# PixelScreen_WS2812B.net
KiCad netlist of a schematic drawn in EasyEDA Pro
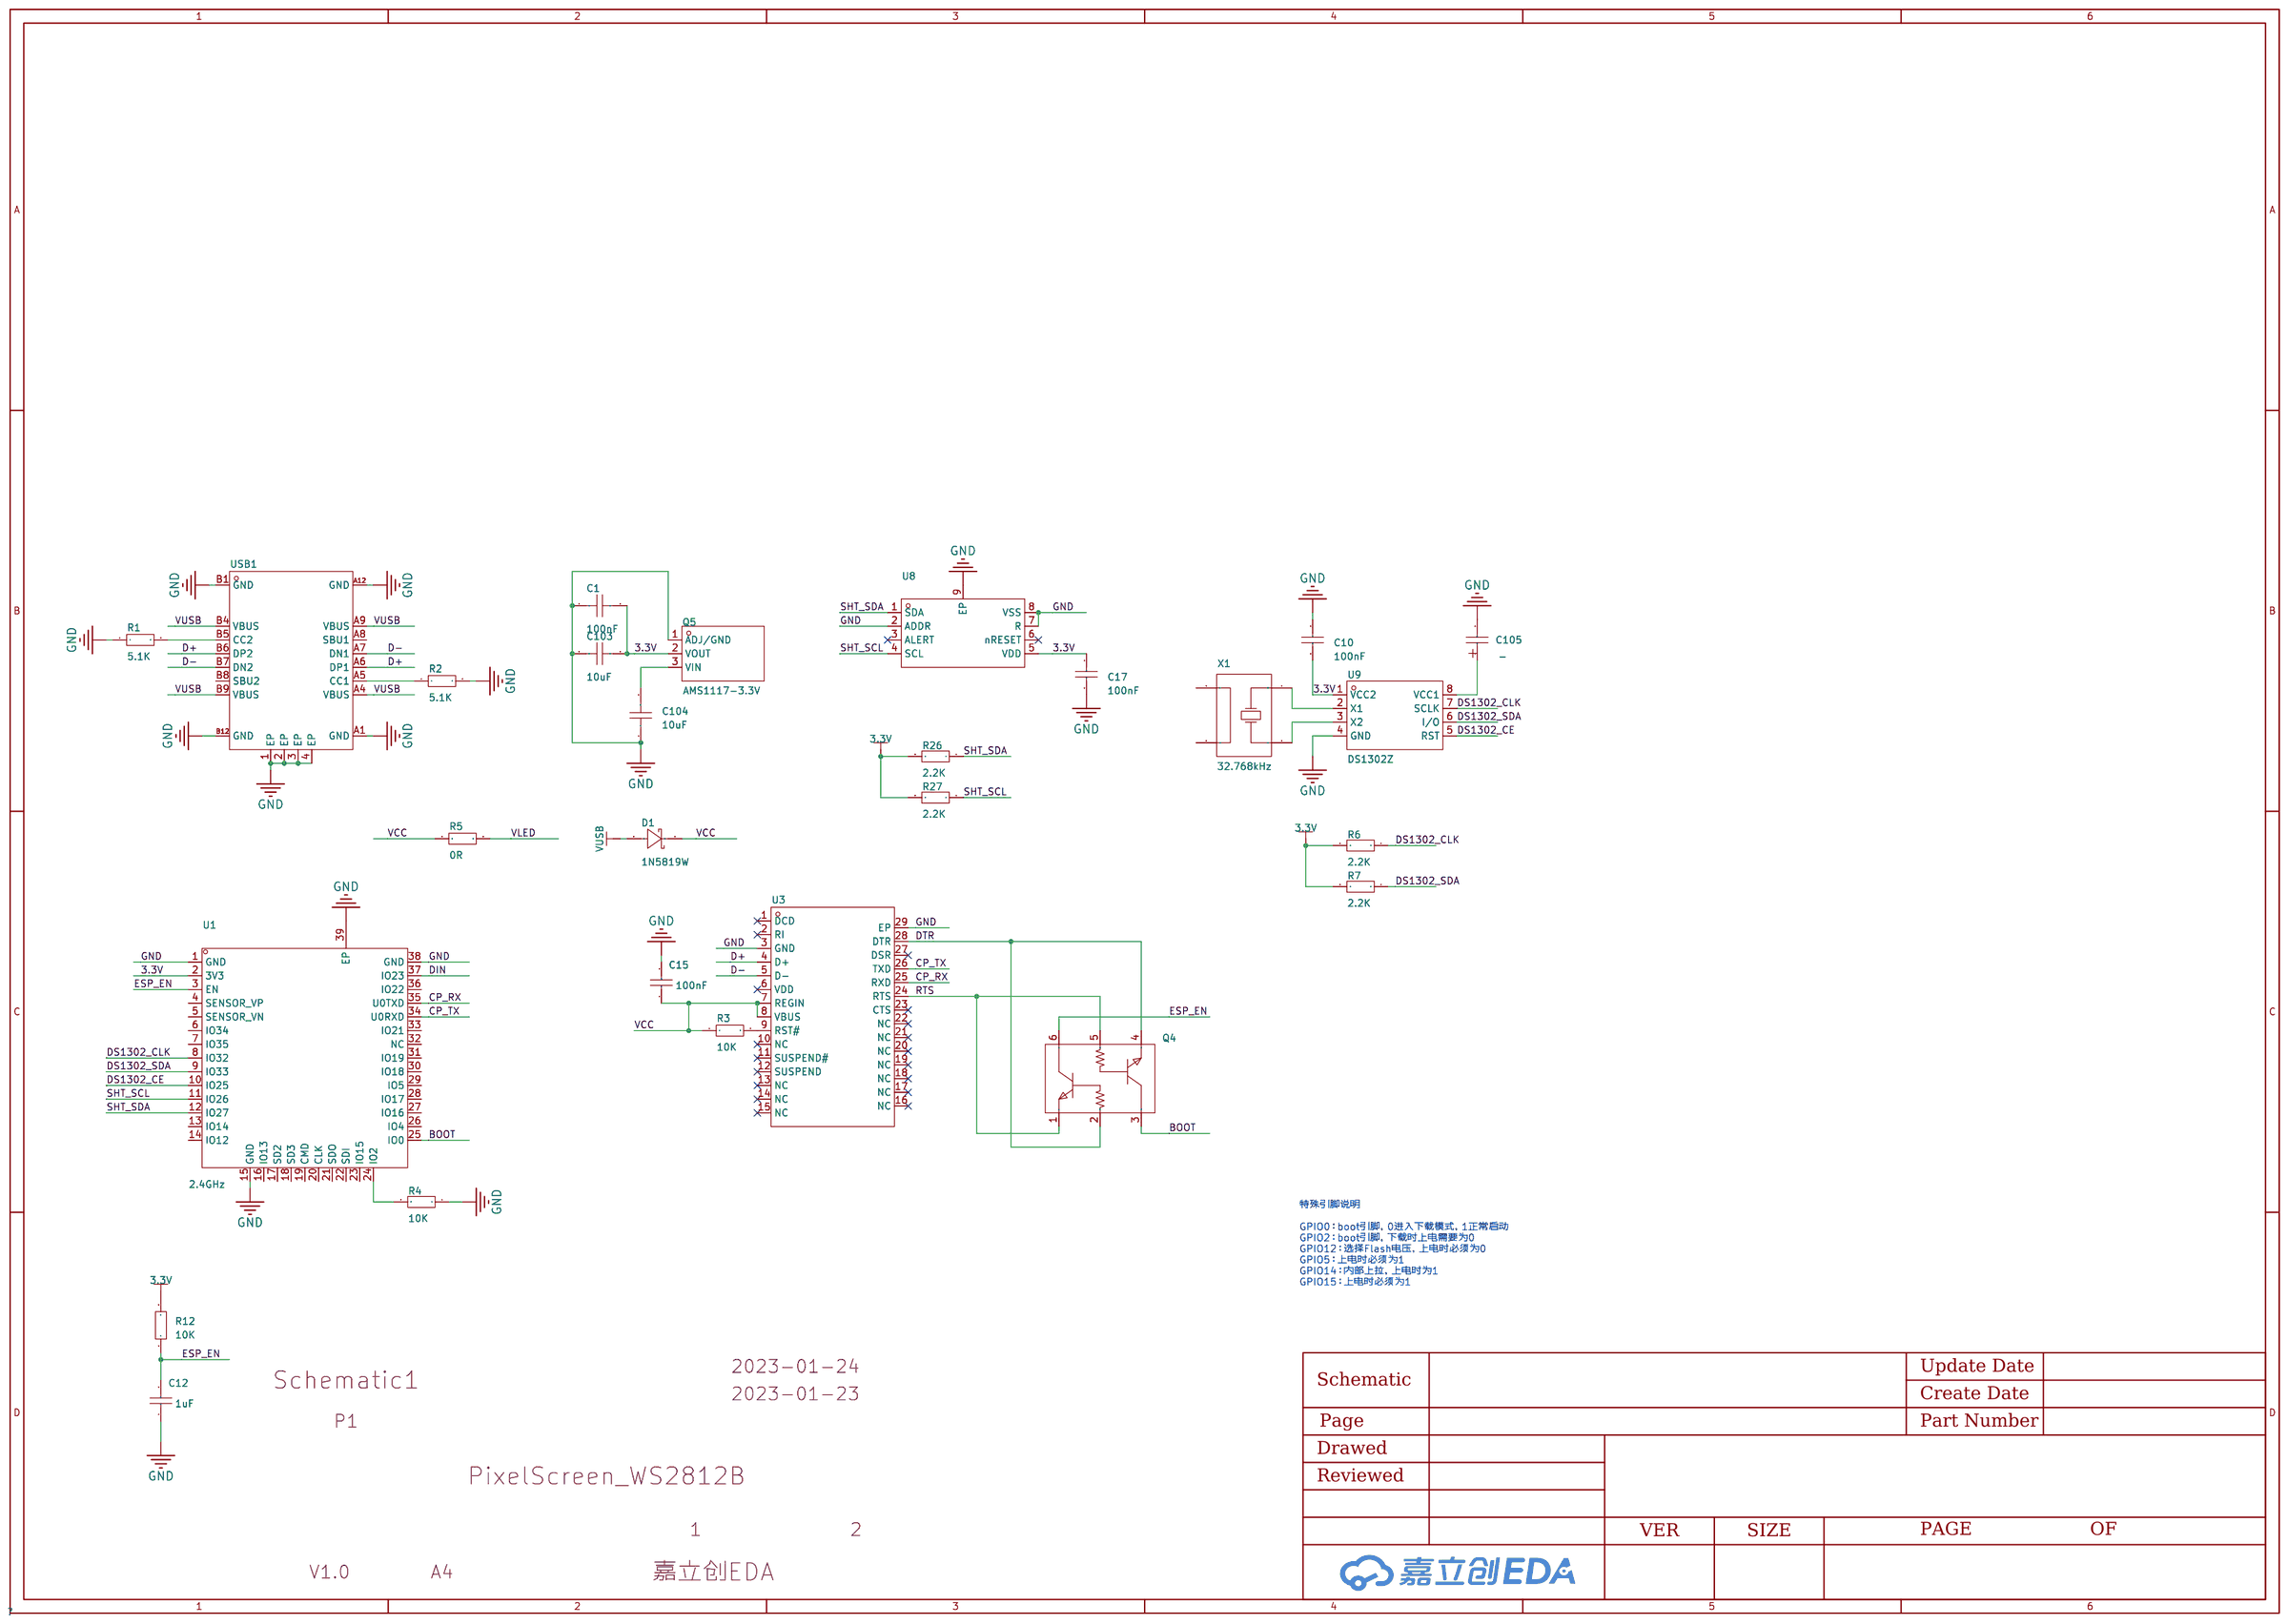
[diagram p0: P1]
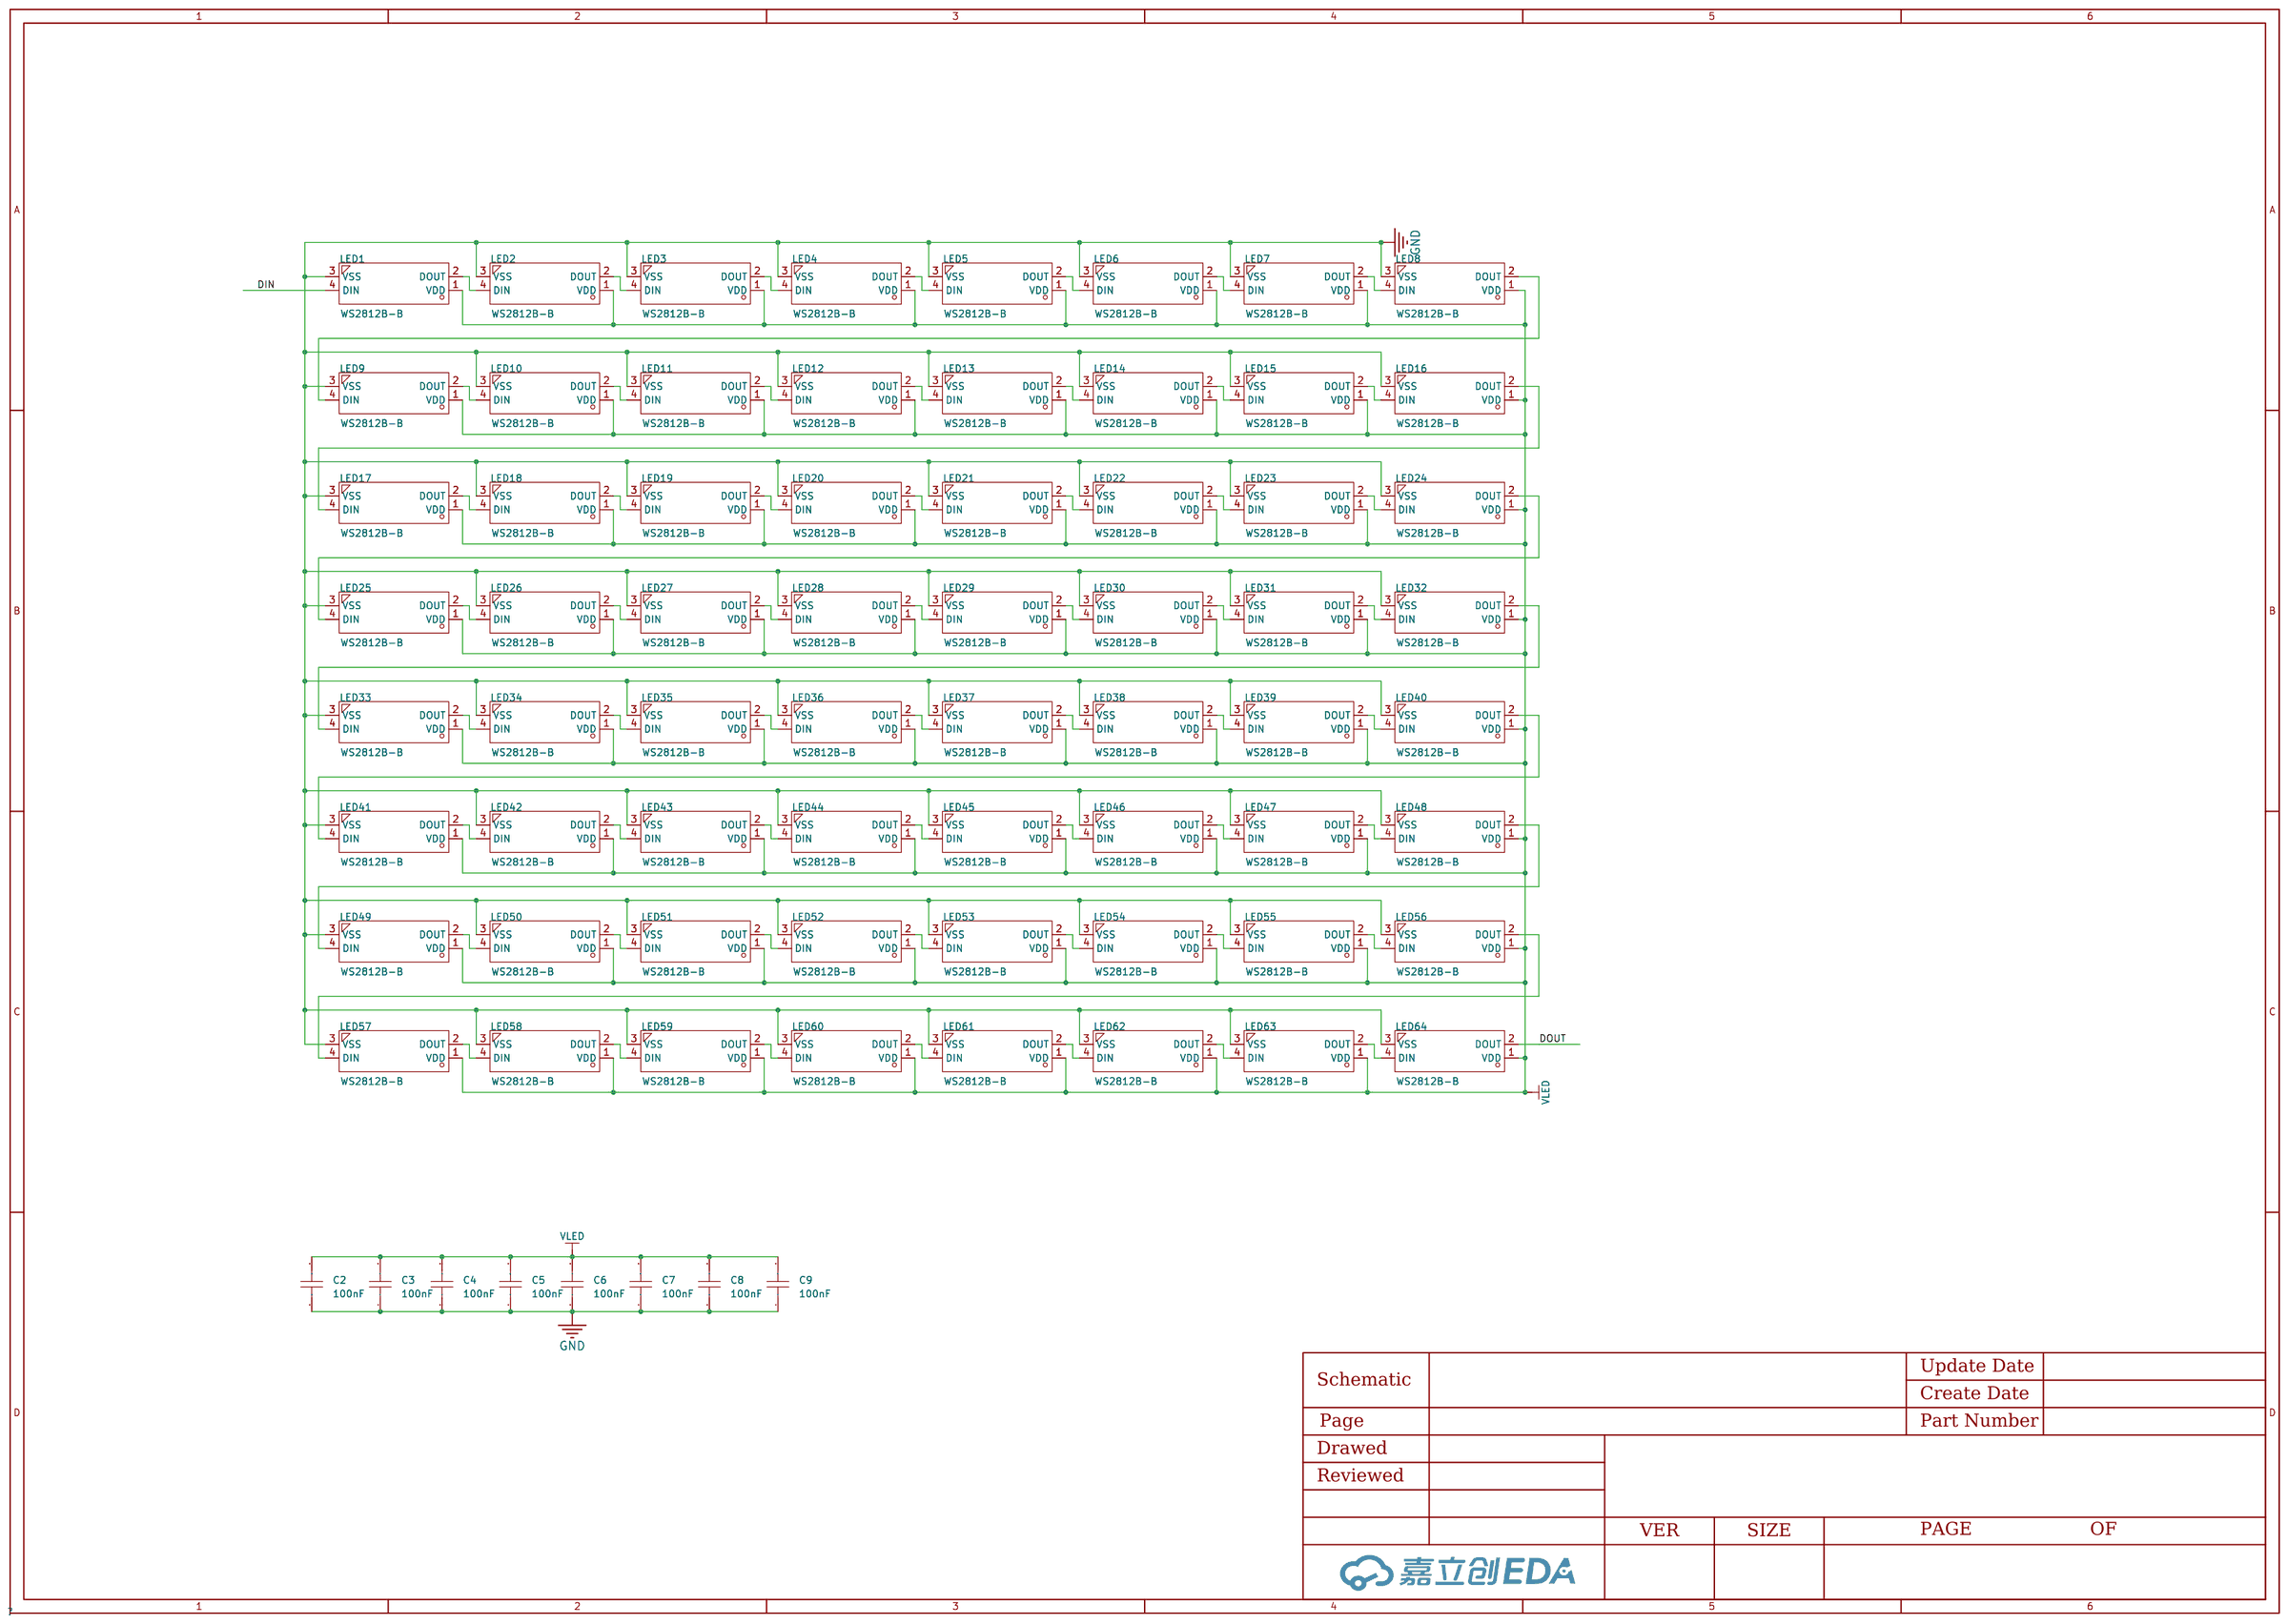
[diagram p1: P2]

(export (version "E")
  (design (tool "Eeschema 10.0.6"))
  (components
    (comp (ref "C1")
      (value "100nF")
      (footprint "easyedapro:C0603")
      (libsource (lib "easyedapro") (part "CapAcitance"))
    )
    (comp (ref "C10")
      (value "100nF")
      (footprint "easyedapro:C0402_NEW")
      (description "容值:100nF;精度:±10%;额定电压:16V;材质(温度系数):X7R;")
      (fields
        (field (name "Manufacturer Part") "CL05B104KO5NNNC")
        (field (name "Manufacturer") "SAMSUNG(三星)")
      )
      (libsource (lib "easyedapro") (part "CL05B104KO5NNNC"))
    )
    (comp (ref "C12")
      (value "1uF")
      (footprint "easyedapro:C0402_NEW")
      (description "容值:100nF;精度:±10%;额定电压:16V;材质(温度系数):X7R;")
      (fields
        (field (name "Manufacturer Part") "CL05B104KO5NNNC")
        (field (name "Manufacturer") "SAMSUNG(三星)")
      )
      (libsource (lib "easyedapro") (part "CL05B104KO5NNNC"))
    )
    (comp (ref "C15")
      (value "100nF")
      (footprint "easyedapro:C0402_NEW")
      (description "容值:100nF;精度:±10%;额定电压:16V;材质(温度系数):X7R;")
      (fields
        (field (name "Manufacturer Part") "CL05B104KO5NNNC")
        (field (name "Manufacturer") "SAMSUNG(三星)")
      )
      (libsource (lib "easyedapro") (part "CL05B104KO5NNNC"))
    )
    (comp (ref "C17")
      (value "100nF")
      (footprint "easyedapro:C0402_NEW")
      (description "容值:100nF;精度:±10%;额定电压:16V;材质(温度系数):X7R;")
      (fields
        (field (name "Manufacturer Part") "CL05B104KO5NNNC")
        (field (name "Manufacturer") "SAMSUNG(三星)")
      )
      (libsource (lib "easyedapro") (part "CL05B104KO5NNNC"))
    )
    (comp (ref "C103")
      (value "10uF")
      (footprint "easyedapro:C0603")
      (libsource (lib "easyedapro") (part "CapAcitance"))
    )
    (comp (ref "C104")
      (value "10uF")
      (footprint "easyedapro:C0603")
      (libsource (lib "easyedapro") (part "CapAcitance"))
    )
    (comp (ref "C105")
      (value "-")
      (footprint "easyedapro:CAP-TH_DMS3R3224")
      (description "容值:-;精度:-;额定电压:-;等效串联电阻:-;漏电流:-;工作寿命:-;循环寿命:-;工作温度:-;电容体直径:-;电容体高:-;")
      (fields (field (name "Manufacturer Part") "DMS3R3224R") (field (name "Manufacturer") "KORCHIP(高奇普)"))
      (libsource (lib "easyedapro") (part "DMS3R3224"))
    )
    (comp (ref "D1")
      (value "1N5819W")
      (footprint "easyedapro:SOD-123_L2.7-W1.6-LS3.7-RD-1")
      (description "二极管配置:-;直流反向耐压(Vr):40V;平均整流电流(Io):1A;正向压降(Vf):900mV@3A;反向电流(Ir):1mA@40V;")
      (fields (field (name "Manufacturer") "TECH PUBLIC(台舟)"))
      (libsource (lib "easyedapro") (part "1N5819W_C2905650"))
    )
    (comp (ref "Q4")
      (value "UMH3N")
      (footprint "easyedapro:SC-70-6_L2.2-W1.3-P0.65-LS2.1-BR")
      (description "晶体管类型:2个NPN-预偏置;功率(Pd):150mW;集电极电流(Ic):100mA;集射极击穿电压(Vceo):50V;")
      (fields (field (name "Manufacturer") "CJ(江苏长电/长晶)"))
      (libsource (lib "easyedapro") (part "UMH3N"))
    )
    (comp (ref "Q5")
      (value "AMS1117-3.3V")
      (footprint "easyedapro:SOT-89-3_L4.5-W2.5-P1.50-LS4.2-BR")
      (description "输出类型:固定;输出极性:正;输出通道数:1;最大输入电压:18V;输出电压:3.3V;压差:1.4V@(1A);静态电流(地电流):12mA;输出电流:1A;工作温度:0℃~+125℃;")
      (fields (field (name "Manufacturer") "MSKSEMI(美森科)"))
      (libsource (lib "easyedapro") (part "AMS1117-3.3V_C5120796"))
    )
    (comp (ref "R1") (value "5.1K") (footprint "easyedapro:R0402") (libsource (lib "easyedapro") (part "电阻")))
    (comp (ref "R2") (value "5.1K") (footprint "easyedapro:R0402") (libsource (lib "easyedapro") (part "电阻")))
    (comp (ref "R3") (value "10K") (footprint "easyedapro:R0402") (libsource (lib "easyedapro") (part "电阻")))
    (comp (ref "R4") (value "10K") (footprint "easyedapro:R0402") (libsource (lib "easyedapro") (part "电阻")))
    (comp (ref "R5") (value "0R") (footprint "easyedapro:R0402") (libsource (lib "easyedapro") (part "电阻")))
    (comp (ref "R6") (value "2.2K") (footprint "easyedapro:R0402") (libsource (lib "easyedapro") (part "电阻")))
    (comp (ref "R7") (value "2.2K") (footprint "easyedapro:R0402") (libsource (lib "easyedapro") (part "电阻")))
    (comp (ref "R12") (value "10K") (footprint "easyedapro:R0402") (libsource (lib "easyedapro") (part "电阻")))
    (comp (ref "R26")
      (value "2.2K")
      (footprint "easyedapro:R0402")
      (libsource (lib "easyedapro") (part "电阻"))
    )
    (comp (ref "R27")
      (value "2.2K")
      (footprint "easyedapro:R0402")
      (libsource (lib "easyedapro") (part "电阻"))
    )
    (comp (ref "U1")
      (value "2.4GHz")
      (footprint "easyedapro:WIRELM-SMD_ESP32-S")
      (description "频率:2.4GHz;发射功率:17dBm;核心处理器:LX6;天线形式:板载 PCB 天线/外接 IPEX;接收灵敏度:-90dBm;")
      (fields (field (name "Manufacturer Part") "ESP32-S") (field (name "Manufacturer") "Ai-Thinker(安信可)"))
      (libsource (lib "easyedapro") (part "ESP32-S"))
    )
    (comp (ref "U3")
      (value "~")
      (footprint "easyedapro:QFN-28_L5.0-W5.0-P0.50-TL-EP3.2")
      (fields (field (name "Manufacturer Part") "CP2102"))
      (libsource (lib "easyedapro") (part "CP2102"))
    )
    (comp (ref "U8")
      (value "~")
      (footprint "easyedapro:DFN-8_L2.5-W2.5-P0.50-BL-EP")
      (description "传感器类型:-;输出类型:-;温度范围:-;湿度范围:-;精度:-;")
      (fields
        (field (name "Manufacturer Part") "SHT30-DIS-B10KS")
        (field (name "Manufacturer") "Sensirion(瑞士盛思锐)")
      )
      (libsource (lib "easyedapro") (part "SHT30-DIS-B10KS"))
    )
    (comp (ref "U9")
      (value "DS1302Z")
      (footprint "easyedapro:SOP-8_L4.9-W3.9-P1.27-LS6.0-BL-1")
      (fields (field (name "Manufacturer") "JSMSEMI(杰盛微)"))
      (libsource (lib "easyedapro") (part "DS1302Z"))
    )
    (comp (ref "USB1")
      (value "~")
      (footprint "easyedapro:USB-C-SMD_KH-TYPE-C-16P")
      (fields (field (name "Manufacturer Part") "typec"))
      (libsource (lib "easyedapro") (part "TYPEC_C9900016956"))
    )
    (comp (ref "X1")
      (value "32.768kHz")
      (footprint "easyedapro:MC-146_4P-L6.7-W1.5-P0.85-TL")
      (description "晶振类型:贴片无源晶振;频率:32.768kHz;频率公差:±20ppm;负载电容:7pF;等效串联电阻(ESR):65kΩ;工作温度:-40℃~+85℃;")
      (fields
        (field (name "Manufacturer Part") "MC-14632.768kHz7.0pF20PPM")
        (field (name "Manufacturer") "EPSON(爱普生)")
      )
      (libsource (lib "easyedapro") (part "MC-14632.768kHz7.0pF20PPM"))
    )
    (comp (ref "C2")
      (value "100nF")
      (footprint "easyedapro:C0603")
      (libsource (lib "easyedapro") (part "CapAcitance"))
    )
    (comp (ref "C3")
      (value "100nF")
      (footprint "easyedapro:C0603")
      (libsource (lib "easyedapro") (part "CapAcitance"))
    )
    (comp (ref "C4")
      (value "100nF")
      (footprint "easyedapro:C0603")
      (libsource (lib "easyedapro") (part "CapAcitance"))
    )
    (comp (ref "C5")
      (value "100nF")
      (footprint "easyedapro:C0603")
      (libsource (lib "easyedapro") (part "CapAcitance"))
    )
    (comp (ref "C6")
      (value "100nF")
      (footprint "easyedapro:C0603")
      (libsource (lib "easyedapro") (part "CapAcitance"))
    )
    (comp (ref "C7")
      (value "100nF")
      (footprint "easyedapro:C0603")
      (libsource (lib "easyedapro") (part "CapAcitance"))
    )
    (comp (ref "C8")
      (value "100nF")
      (footprint "easyedapro:C0603")
      (libsource (lib "easyedapro") (part "CapAcitance"))
    )
    (comp (ref "C9")
      (value "100nF")
      (footprint "easyedapro:C0603")
      (libsource (lib "easyedapro") (part "CapAcitance"))
    )
    (comp (ref "LED1")
      (value "WS2812B-B")
      (footprint "easyedapro:LED-SMD_4P-L5.0-W5.0-BL_TC5050RGB")
      (description "发光颜色:RGB三色;")
      (fields (field (name "Manufacturer") "worldsemi"))
      (libsource (lib "easyedapro") (part "WS2812B-B"))
    )
    (comp (ref "LED2")
      (value "WS2812B-B")
      (footprint "easyedapro:LED-SMD_4P-L5.0-W5.0-BL_TC5050RGB")
      (description "发光颜色:RGB三色;")
      (fields (field (name "Manufacturer") "worldsemi"))
      (libsource (lib "easyedapro") (part "WS2812B-B"))
    )
    (comp (ref "LED3")
      (value "WS2812B-B")
      (footprint "easyedapro:LED-SMD_4P-L5.0-W5.0-BL_TC5050RGB")
      (description "发光颜色:RGB三色;")
      (fields (field (name "Manufacturer") "worldsemi"))
      (libsource (lib "easyedapro") (part "WS2812B-B"))
    )
    (comp (ref "LED4")
      (value "WS2812B-B")
      (footprint "easyedapro:LED-SMD_4P-L5.0-W5.0-BL_TC5050RGB")
      (description "发光颜色:RGB三色;")
      (fields (field (name "Manufacturer") "worldsemi"))
      (libsource (lib "easyedapro") (part "WS2812B-B"))
    )
    (comp (ref "LED5")
      (value "WS2812B-B")
      (footprint "easyedapro:LED-SMD_4P-L5.0-W5.0-BL_TC5050RGB")
      (description "发光颜色:RGB三色;")
      (fields (field (name "Manufacturer") "worldsemi"))
      (libsource (lib "easyedapro") (part "WS2812B-B"))
    )
    (comp (ref "LED6")
      (value "WS2812B-B")
      (footprint "easyedapro:LED-SMD_4P-L5.0-W5.0-BL_TC5050RGB")
      (description "发光颜色:RGB三色;")
      (fields (field (name "Manufacturer") "worldsemi"))
      (libsource (lib "easyedapro") (part "WS2812B-B"))
    )
    (comp (ref "LED7")
      (value "WS2812B-B")
      (footprint "easyedapro:LED-SMD_4P-L5.0-W5.0-BL_TC5050RGB")
      (description "发光颜色:RGB三色;")
      (fields (field (name "Manufacturer") "worldsemi"))
      (libsource (lib "easyedapro") (part "WS2812B-B"))
    )
    (comp (ref "LED8")
      (value "WS2812B-B")
      (footprint "easyedapro:LED-SMD_4P-L5.0-W5.0-BL_TC5050RGB")
      (description "发光颜色:RGB三色;")
      (fields (field (name "Manufacturer") "worldsemi"))
      (libsource (lib "easyedapro") (part "WS2812B-B"))
    )
    (comp (ref "LED9")
      (value "WS2812B-B")
      (footprint "easyedapro:LED-SMD_4P-L5.0-W5.0-BL_TC5050RGB")
      (description "发光颜色:RGB三色;")
      (fields (field (name "Manufacturer") "worldsemi"))
      (libsource (lib "easyedapro") (part "WS2812B-B"))
    )
    (comp (ref "LED10")
      (value "WS2812B-B")
      (footprint "easyedapro:LED-SMD_4P-L5.0-W5.0-BL_TC5050RGB")
      (description "发光颜色:RGB三色;")
      (fields (field (name "Manufacturer") "worldsemi"))
      (libsource (lib "easyedapro") (part "WS2812B-B"))
    )
    (comp (ref "LED11")
      (value "WS2812B-B")
      (footprint "easyedapro:LED-SMD_4P-L5.0-W5.0-BL_TC5050RGB")
      (description "发光颜色:RGB三色;")
      (fields (field (name "Manufacturer") "worldsemi"))
      (libsource (lib "easyedapro") (part "WS2812B-B"))
    )
    (comp (ref "LED12")
      (value "WS2812B-B")
      (footprint "easyedapro:LED-SMD_4P-L5.0-W5.0-BL_TC5050RGB")
      (description "发光颜色:RGB三色;")
      (fields (field (name "Manufacturer") "worldsemi"))
      (libsource (lib "easyedapro") (part "WS2812B-B"))
    )
    (comp (ref "LED13")
      (value "WS2812B-B")
      (footprint "easyedapro:LED-SMD_4P-L5.0-W5.0-BL_TC5050RGB")
      (description "发光颜色:RGB三色;")
      (fields (field (name "Manufacturer") "worldsemi"))
      (libsource (lib "easyedapro") (part "WS2812B-B"))
    )
    (comp (ref "LED14")
      (value "WS2812B-B")
      (footprint "easyedapro:LED-SMD_4P-L5.0-W5.0-BL_TC5050RGB")
      (description "发光颜色:RGB三色;")
      (fields (field (name "Manufacturer") "worldsemi"))
      (libsource (lib "easyedapro") (part "WS2812B-B"))
    )
    (comp (ref "LED15")
      (value "WS2812B-B")
      (footprint "easyedapro:LED-SMD_4P-L5.0-W5.0-BL_TC5050RGB")
      (description "发光颜色:RGB三色;")
      (fields (field (name "Manufacturer") "worldsemi"))
      (libsource (lib "easyedapro") (part "WS2812B-B"))
    )
    (comp (ref "LED16")
      (value "WS2812B-B")
      (footprint "easyedapro:LED-SMD_4P-L5.0-W5.0-BL_TC5050RGB")
      (description "发光颜色:RGB三色;")
      (fields (field (name "Manufacturer") "worldsemi"))
      (libsource (lib "easyedapro") (part "WS2812B-B"))
    )
    (comp (ref "LED17")
      (value "WS2812B-B")
      (footprint "easyedapro:LED-SMD_4P-L5.0-W5.0-BL_TC5050RGB")
      (description "发光颜色:RGB三色;")
      (fields (field (name "Manufacturer") "worldsemi"))
      (libsource (lib "easyedapro") (part "WS2812B-B"))
    )
    (comp (ref "LED18")
      (value "WS2812B-B")
      (footprint "easyedapro:LED-SMD_4P-L5.0-W5.0-BL_TC5050RGB")
      (description "发光颜色:RGB三色;")
      (fields (field (name "Manufacturer") "worldsemi"))
      (libsource (lib "easyedapro") (part "WS2812B-B"))
    )
    (comp (ref "LED19")
      (value "WS2812B-B")
      (footprint "easyedapro:LED-SMD_4P-L5.0-W5.0-BL_TC5050RGB")
      (description "发光颜色:RGB三色;")
      (fields (field (name "Manufacturer") "worldsemi"))
      (libsource (lib "easyedapro") (part "WS2812B-B"))
    )
    (comp (ref "LED20")
      (value "WS2812B-B")
      (footprint "easyedapro:LED-SMD_4P-L5.0-W5.0-BL_TC5050RGB")
      (description "发光颜色:RGB三色;")
      (fields (field (name "Manufacturer") "worldsemi"))
      (libsource (lib "easyedapro") (part "WS2812B-B"))
    )
    (comp (ref "LED21")
      (value "WS2812B-B")
      (footprint "easyedapro:LED-SMD_4P-L5.0-W5.0-BL_TC5050RGB")
      (description "发光颜色:RGB三色;")
      (fields (field (name "Manufacturer") "worldsemi"))
      (libsource (lib "easyedapro") (part "WS2812B-B"))
    )
    (comp (ref "LED22")
      (value "WS2812B-B")
      (footprint "easyedapro:LED-SMD_4P-L5.0-W5.0-BL_TC5050RGB")
      (description "发光颜色:RGB三色;")
      (fields (field (name "Manufacturer") "worldsemi"))
      (libsource (lib "easyedapro") (part "WS2812B-B"))
    )
    (comp (ref "LED23")
      (value "WS2812B-B")
      (footprint "easyedapro:LED-SMD_4P-L5.0-W5.0-BL_TC5050RGB")
      (description "发光颜色:RGB三色;")
      (fields (field (name "Manufacturer") "worldsemi"))
      (libsource (lib "easyedapro") (part "WS2812B-B"))
    )
    (comp (ref "LED24")
      (value "WS2812B-B")
      (footprint "easyedapro:LED-SMD_4P-L5.0-W5.0-BL_TC5050RGB")
      (description "发光颜色:RGB三色;")
      (fields (field (name "Manufacturer") "worldsemi"))
      (libsource (lib "easyedapro") (part "WS2812B-B"))
    )
    (comp (ref "LED25")
      (value "WS2812B-B")
      (footprint "easyedapro:LED-SMD_4P-L5.0-W5.0-BL_TC5050RGB")
      (description "发光颜色:RGB三色;")
      (fields (field (name "Manufacturer") "worldsemi"))
      (libsource (lib "easyedapro") (part "WS2812B-B"))
    )
    (comp (ref "LED26")
      (value "WS2812B-B")
      (footprint "easyedapro:LED-SMD_4P-L5.0-W5.0-BL_TC5050RGB")
      (description "发光颜色:RGB三色;")
      (fields (field (name "Manufacturer") "worldsemi"))
      (libsource (lib "easyedapro") (part "WS2812B-B"))
    )
    (comp (ref "LED27")
      (value "WS2812B-B")
      (footprint "easyedapro:LED-SMD_4P-L5.0-W5.0-BL_TC5050RGB")
      (description "发光颜色:RGB三色;")
      (fields (field (name "Manufacturer") "worldsemi"))
      (libsource (lib "easyedapro") (part "WS2812B-B"))
    )
    (comp (ref "LED28")
      (value "WS2812B-B")
      (footprint "easyedapro:LED-SMD_4P-L5.0-W5.0-BL_TC5050RGB")
      (description "发光颜色:RGB三色;")
      (fields (field (name "Manufacturer") "worldsemi"))
      (libsource (lib "easyedapro") (part "WS2812B-B"))
    )
    (comp (ref "LED29")
      (value "WS2812B-B")
      (footprint "easyedapro:LED-SMD_4P-L5.0-W5.0-BL_TC5050RGB")
      (description "发光颜色:RGB三色;")
      (fields (field (name "Manufacturer") "worldsemi"))
      (libsource (lib "easyedapro") (part "WS2812B-B"))
    )
    (comp (ref "LED30")
      (value "WS2812B-B")
      (footprint "easyedapro:LED-SMD_4P-L5.0-W5.0-BL_TC5050RGB")
      (description "发光颜色:RGB三色;")
      (fields (field (name "Manufacturer") "worldsemi"))
      (libsource (lib "easyedapro") (part "WS2812B-B"))
    )
    (comp (ref "LED31")
      (value "WS2812B-B")
      (footprint "easyedapro:LED-SMD_4P-L5.0-W5.0-BL_TC5050RGB")
      (description "发光颜色:RGB三色;")
      (fields (field (name "Manufacturer") "worldsemi"))
      (libsource (lib "easyedapro") (part "WS2812B-B"))
    )
    (comp (ref "LED32")
      (value "WS2812B-B")
      (footprint "easyedapro:LED-SMD_4P-L5.0-W5.0-BL_TC5050RGB")
      (description "发光颜色:RGB三色;")
      (fields (field (name "Manufacturer") "worldsemi"))
      (libsource (lib "easyedapro") (part "WS2812B-B"))
    )
    (comp (ref "LED33")
      (value "WS2812B-B")
      (footprint "easyedapro:LED-SMD_4P-L5.0-W5.0-BL_TC5050RGB")
      (description "发光颜色:RGB三色;")
      (fields (field (name "Manufacturer") "worldsemi"))
      (libsource (lib "easyedapro") (part "WS2812B-B"))
    )
    (comp (ref "LED34")
      (value "WS2812B-B")
      (footprint "easyedapro:LED-SMD_4P-L5.0-W5.0-BL_TC5050RGB")
      (description "发光颜色:RGB三色;")
      (fields (field (name "Manufacturer") "worldsemi"))
      (libsource (lib "easyedapro") (part "WS2812B-B"))
    )
    (comp (ref "LED35")
      (value "WS2812B-B")
      (footprint "easyedapro:LED-SMD_4P-L5.0-W5.0-BL_TC5050RGB")
      (description "发光颜色:RGB三色;")
      (fields (field (name "Manufacturer") "worldsemi"))
      (libsource (lib "easyedapro") (part "WS2812B-B"))
    )
    (comp (ref "LED36")
      (value "WS2812B-B")
      (footprint "easyedapro:LED-SMD_4P-L5.0-W5.0-BL_TC5050RGB")
      (description "发光颜色:RGB三色;")
      (fields (field (name "Manufacturer") "worldsemi"))
      (libsource (lib "easyedapro") (part "WS2812B-B"))
    )
    (comp (ref "LED37")
      (value "WS2812B-B")
      (footprint "easyedapro:LED-SMD_4P-L5.0-W5.0-BL_TC5050RGB")
      (description "发光颜色:RGB三色;")
      (fields (field (name "Manufacturer") "worldsemi"))
      (libsource (lib "easyedapro") (part "WS2812B-B"))
    )
    (comp (ref "LED38")
      (value "WS2812B-B")
      (footprint "easyedapro:LED-SMD_4P-L5.0-W5.0-BL_TC5050RGB")
      (description "发光颜色:RGB三色;")
      (fields (field (name "Manufacturer") "worldsemi"))
      (libsource (lib "easyedapro") (part "WS2812B-B"))
    )
    (comp (ref "LED39")
      (value "WS2812B-B")
      (footprint "easyedapro:LED-SMD_4P-L5.0-W5.0-BL_TC5050RGB")
      (description "发光颜色:RGB三色;")
      (fields (field (name "Manufacturer") "worldsemi"))
      (libsource (lib "easyedapro") (part "WS2812B-B"))
    )
    (comp (ref "LED40")
      (value "WS2812B-B")
      (footprint "easyedapro:LED-SMD_4P-L5.0-W5.0-BL_TC5050RGB")
      (description "发光颜色:RGB三色;")
      (fields (field (name "Manufacturer") "worldsemi"))
      (libsource (lib "easyedapro") (part "WS2812B-B"))
    )
    (comp (ref "LED41")
      (value "WS2812B-B")
      (footprint "easyedapro:LED-SMD_4P-L5.0-W5.0-BL_TC5050RGB")
      (description "发光颜色:RGB三色;")
      (fields (field (name "Manufacturer") "worldsemi"))
      (libsource (lib "easyedapro") (part "WS2812B-B"))
    )
    (comp (ref "LED42")
      (value "WS2812B-B")
      (footprint "easyedapro:LED-SMD_4P-L5.0-W5.0-BL_TC5050RGB")
      (description "发光颜色:RGB三色;")
      (fields (field (name "Manufacturer") "worldsemi"))
      (libsource (lib "easyedapro") (part "WS2812B-B"))
    )
    (comp (ref "LED43")
      (value "WS2812B-B")
      (footprint "easyedapro:LED-SMD_4P-L5.0-W5.0-BL_TC5050RGB")
      (description "发光颜色:RGB三色;")
      (fields (field (name "Manufacturer") "worldsemi"))
      (libsource (lib "easyedapro") (part "WS2812B-B"))
    )
    (comp (ref "LED44")
      (value "WS2812B-B")
      (footprint "easyedapro:LED-SMD_4P-L5.0-W5.0-BL_TC5050RGB")
      (description "发光颜色:RGB三色;")
      (fields (field (name "Manufacturer") "worldsemi"))
      (libsource (lib "easyedapro") (part "WS2812B-B"))
    )
    (comp (ref "LED45")
      (value "WS2812B-B")
      (footprint "easyedapro:LED-SMD_4P-L5.0-W5.0-BL_TC5050RGB")
      (description "发光颜色:RGB三色;")
      (fields (field (name "Manufacturer") "worldsemi"))
      (libsource (lib "easyedapro") (part "WS2812B-B"))
    )
    (comp (ref "LED46")
      (value "WS2812B-B")
      (footprint "easyedapro:LED-SMD_4P-L5.0-W5.0-BL_TC5050RGB")
      (description "发光颜色:RGB三色;")
      (fields (field (name "Manufacturer") "worldsemi"))
      (libsource (lib "easyedapro") (part "WS2812B-B"))
    )
    (comp (ref "LED47")
      (value "WS2812B-B")
      (footprint "easyedapro:LED-SMD_4P-L5.0-W5.0-BL_TC5050RGB")
      (description "发光颜色:RGB三色;")
      (fields (field (name "Manufacturer") "worldsemi"))
      (libsource (lib "easyedapro") (part "WS2812B-B"))
    )
    (comp (ref "LED48")
      (value "WS2812B-B")
      (footprint "easyedapro:LED-SMD_4P-L5.0-W5.0-BL_TC5050RGB")
      (description "发光颜色:RGB三色;")
      (fields (field (name "Manufacturer") "worldsemi"))
      (libsource (lib "easyedapro") (part "WS2812B-B"))
    )
    (comp (ref "LED49")
      (value "WS2812B-B")
      (footprint "easyedapro:LED-SMD_4P-L5.0-W5.0-BL_TC5050RGB")
      (description "发光颜色:RGB三色;")
      (fields (field (name "Manufacturer") "worldsemi"))
      (libsource (lib "easyedapro") (part "WS2812B-B"))
    )
    (comp (ref "LED50")
      (value "WS2812B-B")
      (footprint "easyedapro:LED-SMD_4P-L5.0-W5.0-BL_TC5050RGB")
      (description "发光颜色:RGB三色;")
      (fields (field (name "Manufacturer") "worldsemi"))
      (libsource (lib "easyedapro") (part "WS2812B-B"))
    )
    (comp (ref "LED51")
      (value "WS2812B-B")
      (footprint "easyedapro:LED-SMD_4P-L5.0-W5.0-BL_TC5050RGB")
      (description "发光颜色:RGB三色;")
      (fields (field (name "Manufacturer") "worldsemi"))
      (libsource (lib "easyedapro") (part "WS2812B-B"))
    )
    (comp (ref "LED52")
      (value "WS2812B-B")
      (footprint "easyedapro:LED-SMD_4P-L5.0-W5.0-BL_TC5050RGB")
      (description "发光颜色:RGB三色;")
      (fields (field (name "Manufacturer") "worldsemi"))
      (libsource (lib "easyedapro") (part "WS2812B-B"))
    )
    (comp (ref "LED53")
      (value "WS2812B-B")
      (footprint "easyedapro:LED-SMD_4P-L5.0-W5.0-BL_TC5050RGB")
      (description "发光颜色:RGB三色;")
      (fields (field (name "Manufacturer") "worldsemi"))
      (libsource (lib "easyedapro") (part "WS2812B-B"))
    )
    (comp (ref "LED54")
      (value "WS2812B-B")
      (footprint "easyedapro:LED-SMD_4P-L5.0-W5.0-BL_TC5050RGB")
      (description "发光颜色:RGB三色;")
      (fields (field (name "Manufacturer") "worldsemi"))
      (libsource (lib "easyedapro") (part "WS2812B-B"))
    )
    (comp (ref "LED55")
      (value "WS2812B-B")
      (footprint "easyedapro:LED-SMD_4P-L5.0-W5.0-BL_TC5050RGB")
      (description "发光颜色:RGB三色;")
      (fields (field (name "Manufacturer") "worldsemi"))
      (libsource (lib "easyedapro") (part "WS2812B-B"))
    )
    (comp (ref "LED56")
      (value "WS2812B-B")
      (footprint "easyedapro:LED-SMD_4P-L5.0-W5.0-BL_TC5050RGB")
      (description "发光颜色:RGB三色;")
      (fields (field (name "Manufacturer") "worldsemi"))
      (libsource (lib "easyedapro") (part "WS2812B-B"))
    )
    (comp (ref "LED57")
      (value "WS2812B-B")
      (footprint "easyedapro:LED-SMD_4P-L5.0-W5.0-BL_TC5050RGB")
      (description "发光颜色:RGB三色;")
      (fields (field (name "Manufacturer") "worldsemi"))
      (libsource (lib "easyedapro") (part "WS2812B-B"))
    )
    (comp (ref "LED58")
      (value "WS2812B-B")
      (footprint "easyedapro:LED-SMD_4P-L5.0-W5.0-BL_TC5050RGB")
      (description "发光颜色:RGB三色;")
      (fields (field (name "Manufacturer") "worldsemi"))
      (libsource (lib "easyedapro") (part "WS2812B-B"))
    )
    (comp (ref "LED59")
      (value "WS2812B-B")
      (footprint "easyedapro:LED-SMD_4P-L5.0-W5.0-BL_TC5050RGB")
      (description "发光颜色:RGB三色;")
      (fields (field (name "Manufacturer") "worldsemi"))
      (libsource (lib "easyedapro") (part "WS2812B-B"))
    )
    (comp (ref "LED60")
      (value "WS2812B-B")
      (footprint "easyedapro:LED-SMD_4P-L5.0-W5.0-BL_TC5050RGB")
      (description "发光颜色:RGB三色;")
      (fields (field (name "Manufacturer") "worldsemi"))
      (libsource (lib "easyedapro") (part "WS2812B-B"))
    )
    (comp (ref "LED61")
      (value "WS2812B-B")
      (footprint "easyedapro:LED-SMD_4P-L5.0-W5.0-BL_TC5050RGB")
      (description "发光颜色:RGB三色;")
      (fields (field (name "Manufacturer") "worldsemi"))
      (libsource (lib "easyedapro") (part "WS2812B-B"))
    )
    (comp (ref "LED62")
      (value "WS2812B-B")
      (footprint "easyedapro:LED-SMD_4P-L5.0-W5.0-BL_TC5050RGB")
      (description "发光颜色:RGB三色;")
      (fields (field (name "Manufacturer") "worldsemi"))
      (libsource (lib "easyedapro") (part "WS2812B-B"))
    )
    (comp (ref "LED63")
      (value "WS2812B-B")
      (footprint "easyedapro:LED-SMD_4P-L5.0-W5.0-BL_TC5050RGB")
      (description "发光颜色:RGB三色;")
      (fields (field (name "Manufacturer") "worldsemi"))
      (libsource (lib "easyedapro") (part "WS2812B-B"))
    )
    (comp (ref "LED64")
      (value "WS2812B-B")
      (footprint "easyedapro:LED-SMD_4P-L5.0-W5.0-BL_TC5050RGB")
      (description "发光颜色:RGB三色;")
      (fields (field (name "Manufacturer") "worldsemi"))
      (libsource (lib "easyedapro") (part "WS2812B-B"))
    )
  )
  (nets
    (net (code "1") (name "3.3V") (class "Default")
      (node (ref "C1") (pin "2") (pinfunction "2_2") (pintype "input"))
      (node (ref "C10") (pin "2") (pinfunction "2_2") (pintype "input"))
      (node (ref "C103") (pin "2") (pinfunction "2_2") (pintype "input"))
      (node (ref "C17") (pin "1") (pinfunction "1_1") (pintype "input"))
      (node (ref "Q5") (pin "2") (pinfunction "VOUT_2") (pintype "input"))
      (node (ref "R12") (pin "2") (pinfunction "2_2") (pintype "input"))
      (node (ref "R26") (pin "2") (pinfunction "2_2") (pintype "input"))
      (node (ref "R27") (pin "2") (pinfunction "2_2") (pintype "input"))
      (node (ref "R6") (pin "2") (pinfunction "2_2") (pintype "input"))
      (node (ref "R7") (pin "2") (pinfunction "2_2") (pintype "input"))
      (node (ref "U1") (pin "2") (pinfunction "3V3_2") (pintype "input"))
      (node (ref "U8") (pin "5") (pinfunction "VDD_5") (pintype "input"))
      (node (ref "U9") (pin "1") (pinfunction "VCC2_1") (pintype "input"))
    )
    (net (code "2") (name "BOOT") (class "Default")
      (node (ref "Q4") (pin "3") (pinfunction "C_3") (pintype "input"))
      (node (ref "U1") (pin "25") (pinfunction "IO0_25") (pintype "input"))
    )
    (net (code "3") (name "CP_RX") (class "Default")
      (node (ref "U1") (pin "35") (pinfunction "U0TXD_35") (pintype "input"))
      (node (ref "U3") (pin "25") (pinfunction "RXD_25") (pintype "input"))
    )
    (net (code "4") (name "CP_TX") (class "Default")
      (node (ref "U1") (pin "34") (pinfunction "U0RXD_34") (pintype "input"))
      (node (ref "U3") (pin "26") (pinfunction "TXD_26") (pintype "input"))
    )
    (net (code "5") (name "D+") (class "Default")
      (node (ref "U3") (pin "4") (pinfunction "D+_4") (pintype "input"))
      (node (ref "USB1") (pin "A6") (pinfunction "DP1_A6") (pintype "input"))
      (node (ref "USB1") (pin "B6") (pinfunction "DP2_B6") (pintype "input"))
    )
    (net (code "6") (name "D-") (class "Default")
      (node (ref "U3") (pin "5") (pinfunction "D-_5") (pintype "input"))
      (node (ref "USB1") (pin "A7") (pinfunction "DN1_A7") (pintype "input"))
      (node (ref "USB1") (pin "B7") (pinfunction "DN2_B7") (pintype "input"))
    )
    (net (code "7") (name "DIN") (class "Default")
      (node (ref "LED1") (pin "4") (pinfunction "DIN_4") (pintype "input"))
      (node (ref "U1") (pin "37") (pinfunction "IO23_37") (pintype "input"))
    )
    (net (code "8") (name "DOUT") (class "Default")
      (node (ref "LED64") (pin "2") (pinfunction "DOUT_2") (pintype "input"))
    )
    (net (code "9") (name "DS1302_CE") (class "Default")
      (node (ref "U1") (pin "10") (pinfunction "IO25_10") (pintype "input"))
      (node (ref "U9") (pin "5") (pinfunction "RST_5") (pintype "input"))
    )
    (net (code "10") (name "DS1302_CLK") (class "Default")
      (node (ref "R6") (pin "1") (pinfunction "1_1") (pintype "input"))
      (node (ref "U1") (pin "8") (pinfunction "IO32_8") (pintype "input"))
      (node (ref "U9") (pin "7") (pinfunction "SCLK_7") (pintype "input"))
    )
    (net (code "11") (name "DS1302_SDA") (class "Default")
      (node (ref "R7") (pin "1") (pinfunction "1_1") (pintype "input"))
      (node (ref "U1") (pin "9") (pinfunction "IO33_9") (pintype "input"))
      (node (ref "U9") (pin "6") (pinfunction "I/O_6") (pintype "input"))
    )
    (net (code "12") (name "DTR") (class "Default")
      (node (ref "Q4") (pin "2") (pinfunction "B_2") (pintype "input"))
      (node (ref "Q4") (pin "4") (pinfunction "E_4") (pintype "input"))
      (node (ref "U3") (pin "28") (pinfunction "DTR_28") (pintype "input"))
    )
    (net (code "13") (name "ESP_EN") (class "Default")
      (node (ref "C12") (pin "2") (pinfunction "2_2") (pintype "input"))
      (node (ref "Q4") (pin "6") (pinfunction "C_6") (pintype "input"))
      (node (ref "R12") (pin "1") (pinfunction "1_1") (pintype "input"))
      (node (ref "U1") (pin "3") (pinfunction "EN_3") (pintype "input"))
    )
    (net (code "14") (name "GND") (class "Default")
      (node (ref "C1") (pin "1") (pinfunction "1_1") (pintype "input"))
      (node (ref "C10") (pin "1") (pinfunction "1_1") (pintype "input"))
      (node (ref "C103") (pin "1") (pinfunction "1_1") (pintype "input"))
      (node (ref "C104") (pin "1") (pinfunction "1_1") (pintype "input"))
      (node (ref "C105") (pin "2") (pinfunction "2_2") (pintype "input"))
      (node (ref "C12") (pin "1") (pinfunction "1_1") (pintype "input"))
      (node (ref "C15") (pin "2") (pinfunction "2_2") (pintype "input"))
      (node (ref "C17") (pin "2") (pinfunction "2_2") (pintype "input"))
      (node (ref "C2") (pin "1") (pinfunction "1_1") (pintype "input"))
      (node (ref "C3") (pin "1") (pinfunction "1_1") (pintype "input"))
      (node (ref "C4") (pin "1") (pinfunction "1_1") (pintype "input"))
      (node (ref "C5") (pin "1") (pinfunction "1_1") (pintype "input"))
      (node (ref "C6") (pin "1") (pinfunction "1_1") (pintype "input"))
      (node (ref "C7") (pin "1") (pinfunction "1_1") (pintype "input"))
      (node (ref "C8") (pin "1") (pinfunction "1_1") (pintype "input"))
      (node (ref "C9") (pin "1") (pinfunction "1_1") (pintype "input"))
      (node (ref "LED1") (pin "3") (pinfunction "VSS_3") (pintype "input"))
      (node (ref "LED10") (pin "3") (pinfunction "VSS_3") (pintype "input"))
      (node (ref "LED11") (pin "3") (pinfunction "VSS_3") (pintype "input"))
      (node (ref "LED12") (pin "3") (pinfunction "VSS_3") (pintype "input"))
      (node (ref "LED13") (pin "3") (pinfunction "VSS_3") (pintype "input"))
      (node (ref "LED14") (pin "3") (pinfunction "VSS_3") (pintype "input"))
      (node (ref "LED15") (pin "3") (pinfunction "VSS_3") (pintype "input"))
      (node (ref "LED16") (pin "3") (pinfunction "VSS_3") (pintype "input"))
      (node (ref "LED17") (pin "3") (pinfunction "VSS_3") (pintype "input"))
      (node (ref "LED18") (pin "3") (pinfunction "VSS_3") (pintype "input"))
      (node (ref "LED19") (pin "3") (pinfunction "VSS_3") (pintype "input"))
      (node (ref "LED2") (pin "3") (pinfunction "VSS_3") (pintype "input"))
      (node (ref "LED20") (pin "3") (pinfunction "VSS_3") (pintype "input"))
      (node (ref "LED21") (pin "3") (pinfunction "VSS_3") (pintype "input"))
      (node (ref "LED22") (pin "3") (pinfunction "VSS_3") (pintype "input"))
      (node (ref "LED23") (pin "3") (pinfunction "VSS_3") (pintype "input"))
      (node (ref "LED24") (pin "3") (pinfunction "VSS_3") (pintype "input"))
      (node (ref "LED25") (pin "3") (pinfunction "VSS_3") (pintype "input"))
      (node (ref "LED26") (pin "3") (pinfunction "VSS_3") (pintype "input"))
      (node (ref "LED27") (pin "3") (pinfunction "VSS_3") (pintype "input"))
      (node (ref "LED28") (pin "3") (pinfunction "VSS_3") (pintype "input"))
      (node (ref "LED29") (pin "3") (pinfunction "VSS_3") (pintype "input"))
      (node (ref "LED3") (pin "3") (pinfunction "VSS_3") (pintype "input"))
      (node (ref "LED30") (pin "3") (pinfunction "VSS_3") (pintype "input"))
      (node (ref "LED31") (pin "3") (pinfunction "VSS_3") (pintype "input"))
      (node (ref "LED32") (pin "3") (pinfunction "VSS_3") (pintype "input"))
      (node (ref "LED33") (pin "3") (pinfunction "VSS_3") (pintype "input"))
      (node (ref "LED34") (pin "3") (pinfunction "VSS_3") (pintype "input"))
      (node (ref "LED35") (pin "3") (pinfunction "VSS_3") (pintype "input"))
      (node (ref "LED36") (pin "3") (pinfunction "VSS_3") (pintype "input"))
      (node (ref "LED37") (pin "3") (pinfunction "VSS_3") (pintype "input"))
      (node (ref "LED38") (pin "3") (pinfunction "VSS_3") (pintype "input"))
      (node (ref "LED39") (pin "3") (pinfunction "VSS_3") (pintype "input"))
      (node (ref "LED4") (pin "3") (pinfunction "VSS_3") (pintype "input"))
      (node (ref "LED40") (pin "3") (pinfunction "VSS_3") (pintype "input"))
      (node (ref "LED41") (pin "3") (pinfunction "VSS_3") (pintype "input"))
      (node (ref "LED42") (pin "3") (pinfunction "VSS_3") (pintype "input"))
      (node (ref "LED43") (pin "3") (pinfunction "VSS_3") (pintype "input"))
      (node (ref "LED44") (pin "3") (pinfunction "VSS_3") (pintype "input"))
      (node (ref "LED45") (pin "3") (pinfunction "VSS_3") (pintype "input"))
      (node (ref "LED46") (pin "3") (pinfunction "VSS_3") (pintype "input"))
      (node (ref "LED47") (pin "3") (pinfunction "VSS_3") (pintype "input"))
      (node (ref "LED48") (pin "3") (pinfunction "VSS_3") (pintype "input"))
      (node (ref "LED49") (pin "3") (pinfunction "VSS_3") (pintype "input"))
      (node (ref "LED5") (pin "3") (pinfunction "VSS_3") (pintype "input"))
      (node (ref "LED50") (pin "3") (pinfunction "VSS_3") (pintype "input"))
      (node (ref "LED51") (pin "3") (pinfunction "VSS_3") (pintype "input"))
      (node (ref "LED52") (pin "3") (pinfunction "VSS_3") (pintype "input"))
      (node (ref "LED53") (pin "3") (pinfunction "VSS_3") (pintype "input"))
      (node (ref "LED54") (pin "3") (pinfunction "VSS_3") (pintype "input"))
      (node (ref "LED55") (pin "3") (pinfunction "VSS_3") (pintype "input"))
      (node (ref "LED56") (pin "3") (pinfunction "VSS_3") (pintype "input"))
      (node (ref "LED57") (pin "3") (pinfunction "VSS_3") (pintype "input"))
      (node (ref "LED58") (pin "3") (pinfunction "VSS_3") (pintype "input"))
      (node (ref "LED59") (pin "3") (pinfunction "VSS_3") (pintype "input"))
      (node (ref "LED6") (pin "3") (pinfunction "VSS_3") (pintype "input"))
      (node (ref "LED60") (pin "3") (pinfunction "VSS_3") (pintype "input"))
      (node (ref "LED61") (pin "3") (pinfunction "VSS_3") (pintype "input"))
      (node (ref "LED62") (pin "3") (pinfunction "VSS_3") (pintype "input"))
      (node (ref "LED63") (pin "3") (pinfunction "VSS_3") (pintype "input"))
      (node (ref "LED64") (pin "3") (pinfunction "VSS_3") (pintype "input"))
      (node (ref "LED7") (pin "3") (pinfunction "VSS_3") (pintype "input"))
      (node (ref "LED8") (pin "3") (pinfunction "VSS_3") (pintype "input"))
      (node (ref "LED9") (pin "3") (pinfunction "VSS_3") (pintype "input"))
      (node (ref "Q5") (pin "1") (pinfunction "ADJ/GND_1") (pintype "input"))
      (node (ref "R1") (pin "1") (pinfunction "1_1") (pintype "input"))
      (node (ref "R2") (pin "2") (pinfunction "2_2") (pintype "input"))
      (node (ref "R4") (pin "1") (pinfunction "1_1") (pintype "input"))
      (node (ref "U1") (pin "1") (pinfunction "GND_1") (pintype "input"))
      (node (ref "U1") (pin "15") (pinfunction "GND_15") (pintype "input"))
      (node (ref "U1") (pin "38") (pinfunction "GND_38") (pintype "input"))
      (node (ref "U1") (pin "39") (pinfunction "EP_39") (pintype "input"))
      (node (ref "U3") (pin "29") (pinfunction "EP_29") (pintype "input"))
      (node (ref "U3") (pin "3") (pinfunction "GND_3") (pintype "input"))
      (node (ref "U8") (pin "2") (pinfunction "ADDR_2") (pintype "input"))
      (node (ref "U8") (pin "7") (pinfunction "R_7") (pintype "input"))
      (node (ref "U8") (pin "8") (pinfunction "VSS_8") (pintype "input"))
      (node (ref "U8") (pin "9") (pinfunction "EP_9") (pintype "input"))
      (node (ref "U9") (pin "4") (pinfunction "GND_4") (pintype "input"))
      (node (ref "USB1") (pin "1") (pinfunction "EP_1") (pintype "input"))
      (node (ref "USB1") (pin "2") (pinfunction "EP_2") (pintype "input"))
      (node (ref "USB1") (pin "3") (pinfunction "EP_3") (pintype "input"))
      (node (ref "USB1") (pin "4") (pinfunction "EP_4") (pintype "input"))
      (node (ref "USB1") (pin "A1") (pinfunction "GND_A1") (pintype "input"))
      (node (ref "USB1") (pin "A12") (pinfunction "GND_A12") (pintype "input"))
      (node (ref "USB1") (pin "B1") (pinfunction "GND_B1") (pintype "input"))
      (node (ref "USB1") (pin "B12") (pinfunction "GND_B12") (pintype "input"))
    )
    (net (code "15") (name "Net-(LED1-DOUT)") (class "Default")
      (node (ref "LED1") (pin "2") (pinfunction "DOUT_2") (pintype "input"))
      (node (ref "LED2") (pin "4") (pinfunction "DIN_4") (pintype "input"))
    )
    (net (code "16") (name "Net-(LED2-DOUT)") (class "Default")
      (node (ref "LED2") (pin "2") (pinfunction "DOUT_2") (pintype "input"))
      (node (ref "LED3") (pin "4") (pinfunction "DIN_4") (pintype "input"))
    )
    (net (code "17") (name "Net-(LED3-DOUT)") (class "Default")
      (node (ref "LED3") (pin "2") (pinfunction "DOUT_2") (pintype "input"))
      (node (ref "LED4") (pin "4") (pinfunction "DIN_4") (pintype "input"))
    )
    (net (code "18") (name "Net-(LED4-DOUT)") (class "Default")
      (node (ref "LED4") (pin "2") (pinfunction "DOUT_2") (pintype "input"))
      (node (ref "LED5") (pin "4") (pinfunction "DIN_4") (pintype "input"))
    )
    (net (code "19") (name "Net-(LED5-DOUT)") (class "Default")
      (node (ref "LED5") (pin "2") (pinfunction "DOUT_2") (pintype "input"))
      (node (ref "LED6") (pin "4") (pinfunction "DIN_4") (pintype "input"))
    )
    (net (code "20") (name "Net-(LED6-DOUT)") (class "Default")
      (node (ref "LED6") (pin "2") (pinfunction "DOUT_2") (pintype "input"))
      (node (ref "LED7") (pin "4") (pinfunction "DIN_4") (pintype "input"))
    )
    (net (code "21") (name "Net-(LED7-DOUT)") (class "Default")
      (node (ref "LED7") (pin "2") (pinfunction "DOUT_2") (pintype "input"))
      (node (ref "LED8") (pin "4") (pinfunction "DIN_4") (pintype "input"))
    )
    (net (code "22") (name "Net-(LED8-DOUT)") (class "Default")
      (node (ref "LED8") (pin "2") (pinfunction "DOUT_2") (pintype "input"))
      (node (ref "LED9") (pin "4") (pinfunction "DIN_4") (pintype "input"))
    )
    (net (code "23") (name "Net-(LED10-DIN)") (class "Default")
      (node (ref "LED10") (pin "4") (pinfunction "DIN_4") (pintype "input"))
      (node (ref "LED9") (pin "2") (pinfunction "DOUT_2") (pintype "input"))
    )
    (net (code "24") (name "Net-(LED10-DOUT)") (class "Default")
      (node (ref "LED10") (pin "2") (pinfunction "DOUT_2") (pintype "input"))
      (node (ref "LED11") (pin "4") (pinfunction "DIN_4") (pintype "input"))
    )
    (net (code "25") (name "Net-(LED11-DOUT)") (class "Default")
      (node (ref "LED11") (pin "2") (pinfunction "DOUT_2") (pintype "input"))
      (node (ref "LED12") (pin "4") (pinfunction "DIN_4") (pintype "input"))
    )
    (net (code "26") (name "Net-(LED12-DOUT)") (class "Default")
      (node (ref "LED12") (pin "2") (pinfunction "DOUT_2") (pintype "input"))
      (node (ref "LED13") (pin "4") (pinfunction "DIN_4") (pintype "input"))
    )
    (net (code "27") (name "Net-(LED13-DOUT)") (class "Default")
      (node (ref "LED13") (pin "2") (pinfunction "DOUT_2") (pintype "input"))
      (node (ref "LED14") (pin "4") (pinfunction "DIN_4") (pintype "input"))
    )
    (net (code "28") (name "Net-(LED14-DOUT)") (class "Default")
      (node (ref "LED14") (pin "2") (pinfunction "DOUT_2") (pintype "input"))
      (node (ref "LED15") (pin "4") (pinfunction "DIN_4") (pintype "input"))
    )
    (net (code "29") (name "Net-(LED15-DOUT)") (class "Default")
      (node (ref "LED15") (pin "2") (pinfunction "DOUT_2") (pintype "input"))
      (node (ref "LED16") (pin "4") (pinfunction "DIN_4") (pintype "input"))
    )
    (net (code "30") (name "Net-(LED16-DOUT)") (class "Default")
      (node (ref "LED16") (pin "2") (pinfunction "DOUT_2") (pintype "input"))
      (node (ref "LED17") (pin "4") (pinfunction "DIN_4") (pintype "input"))
    )
    (net (code "31") (name "Net-(LED17-DOUT)") (class "Default")
      (node (ref "LED17") (pin "2") (pinfunction "DOUT_2") (pintype "input"))
      (node (ref "LED18") (pin "4") (pinfunction "DIN_4") (pintype "input"))
    )
    (net (code "32") (name "Net-(LED18-DOUT)") (class "Default")
      (node (ref "LED18") (pin "2") (pinfunction "DOUT_2") (pintype "input"))
      (node (ref "LED19") (pin "4") (pinfunction "DIN_4") (pintype "input"))
    )
    (net (code "33") (name "Net-(LED19-DOUT)") (class "Default")
      (node (ref "LED19") (pin "2") (pinfunction "DOUT_2") (pintype "input"))
      (node (ref "LED20") (pin "4") (pinfunction "DIN_4") (pintype "input"))
    )
    (net (code "34") (name "Net-(LED20-DOUT)") (class "Default")
      (node (ref "LED20") (pin "2") (pinfunction "DOUT_2") (pintype "input"))
      (node (ref "LED21") (pin "4") (pinfunction "DIN_4") (pintype "input"))
    )
    (net (code "35") (name "Net-(LED21-DOUT)") (class "Default")
      (node (ref "LED21") (pin "2") (pinfunction "DOUT_2") (pintype "input"))
      (node (ref "LED22") (pin "4") (pinfunction "DIN_4") (pintype "input"))
    )
    (net (code "36") (name "Net-(LED22-DOUT)") (class "Default")
      (node (ref "LED22") (pin "2") (pinfunction "DOUT_2") (pintype "input"))
      (node (ref "LED23") (pin "4") (pinfunction "DIN_4") (pintype "input"))
    )
    (net (code "37") (name "Net-(LED23-DOUT)") (class "Default")
      (node (ref "LED23") (pin "2") (pinfunction "DOUT_2") (pintype "input"))
      (node (ref "LED24") (pin "4") (pinfunction "DIN_4") (pintype "input"))
    )
    (net (code "38") (name "Net-(LED24-DOUT)") (class "Default")
      (node (ref "LED24") (pin "2") (pinfunction "DOUT_2") (pintype "input"))
      (node (ref "LED25") (pin "4") (pinfunction "DIN_4") (pintype "input"))
    )
    (net (code "39") (name "Net-(LED25-DOUT)") (class "Default")
      (node (ref "LED25") (pin "2") (pinfunction "DOUT_2") (pintype "input"))
      (node (ref "LED26") (pin "4") (pinfunction "DIN_4") (pintype "input"))
    )
    (net (code "40") (name "Net-(LED26-DOUT)") (class "Default")
      (node (ref "LED26") (pin "2") (pinfunction "DOUT_2") (pintype "input"))
      (node (ref "LED27") (pin "4") (pinfunction "DIN_4") (pintype "input"))
    )
    (net (code "41") (name "Net-(LED27-DOUT)") (class "Default")
      (node (ref "LED27") (pin "2") (pinfunction "DOUT_2") (pintype "input"))
      (node (ref "LED28") (pin "4") (pinfunction "DIN_4") (pintype "input"))
    )
    (net (code "42") (name "Net-(LED28-DOUT)") (class "Default")
      (node (ref "LED28") (pin "2") (pinfunction "DOUT_2") (pintype "input"))
      (node (ref "LED29") (pin "4") (pinfunction "DIN_4") (pintype "input"))
    )
    (net (code "43") (name "Net-(LED29-DOUT)") (class "Default")
      (node (ref "LED29") (pin "2") (pinfunction "DOUT_2") (pintype "input"))
      (node (ref "LED30") (pin "4") (pinfunction "DIN_4") (pintype "input"))
    )
    (net (code "44") (name "Net-(LED30-DOUT)") (class "Default")
      (node (ref "LED30") (pin "2") (pinfunction "DOUT_2") (pintype "input"))
      (node (ref "LED31") (pin "4") (pinfunction "DIN_4") (pintype "input"))
    )
    (net (code "45") (name "Net-(LED31-DOUT)") (class "Default")
      (node (ref "LED31") (pin "2") (pinfunction "DOUT_2") (pintype "input"))
      (node (ref "LED32") (pin "4") (pinfunction "DIN_4") (pintype "input"))
    )
    (net (code "46") (name "Net-(LED32-DOUT)") (class "Default")
      (node (ref "LED32") (pin "2") (pinfunction "DOUT_2") (pintype "input"))
      (node (ref "LED33") (pin "4") (pinfunction "DIN_4") (pintype "input"))
    )
    (net (code "47") (name "Net-(LED33-DOUT)") (class "Default")
      (node (ref "LED33") (pin "2") (pinfunction "DOUT_2") (pintype "input"))
      (node (ref "LED34") (pin "4") (pinfunction "DIN_4") (pintype "input"))
    )
    (net (code "48") (name "Net-(LED34-DOUT)") (class "Default")
      (node (ref "LED34") (pin "2") (pinfunction "DOUT_2") (pintype "input"))
      (node (ref "LED35") (pin "4") (pinfunction "DIN_4") (pintype "input"))
    )
    (net (code "49") (name "Net-(LED35-DOUT)") (class "Default")
      (node (ref "LED35") (pin "2") (pinfunction "DOUT_2") (pintype "input"))
      (node (ref "LED36") (pin "4") (pinfunction "DIN_4") (pintype "input"))
    )
    (net (code "50") (name "Net-(LED36-DOUT)") (class "Default")
      (node (ref "LED36") (pin "2") (pinfunction "DOUT_2") (pintype "input"))
      (node (ref "LED37") (pin "4") (pinfunction "DIN_4") (pintype "input"))
    )
    (net (code "51") (name "Net-(LED37-DOUT)") (class "Default")
      (node (ref "LED37") (pin "2") (pinfunction "DOUT_2") (pintype "input"))
      (node (ref "LED38") (pin "4") (pinfunction "DIN_4") (pintype "input"))
    )
    (net (code "52") (name "Net-(LED38-DOUT)") (class "Default")
      (node (ref "LED38") (pin "2") (pinfunction "DOUT_2") (pintype "input"))
      (node (ref "LED39") (pin "4") (pinfunction "DIN_4") (pintype "input"))
    )
    (net (code "53") (name "Net-(LED39-DOUT)") (class "Default")
      (node (ref "LED39") (pin "2") (pinfunction "DOUT_2") (pintype "input"))
      (node (ref "LED40") (pin "4") (pinfunction "DIN_4") (pintype "input"))
    )
    (net (code "54") (name "Net-(LED40-DOUT)") (class "Default")
      (node (ref "LED40") (pin "2") (pinfunction "DOUT_2") (pintype "input"))
      (node (ref "LED41") (pin "4") (pinfunction "DIN_4") (pintype "input"))
    )
    (net (code "55") (name "Net-(LED41-DOUT)") (class "Default")
      (node (ref "LED41") (pin "2") (pinfunction "DOUT_2") (pintype "input"))
      (node (ref "LED42") (pin "4") (pinfunction "DIN_4") (pintype "input"))
    )
    (net (code "56") (name "Net-(LED42-DOUT)") (class "Default")
      (node (ref "LED42") (pin "2") (pinfunction "DOUT_2") (pintype "input"))
      (node (ref "LED43") (pin "4") (pinfunction "DIN_4") (pintype "input"))
    )
    (net (code "57") (name "Net-(LED43-DOUT)") (class "Default")
      (node (ref "LED43") (pin "2") (pinfunction "DOUT_2") (pintype "input"))
      (node (ref "LED44") (pin "4") (pinfunction "DIN_4") (pintype "input"))
    )
    (net (code "58") (name "Net-(LED44-DOUT)") (class "Default")
      (node (ref "LED44") (pin "2") (pinfunction "DOUT_2") (pintype "input"))
      (node (ref "LED45") (pin "4") (pinfunction "DIN_4") (pintype "input"))
    )
    (net (code "59") (name "Net-(LED45-DOUT)") (class "Default")
      (node (ref "LED45") (pin "2") (pinfunction "DOUT_2") (pintype "input"))
      (node (ref "LED46") (pin "4") (pinfunction "DIN_4") (pintype "input"))
    )
    (net (code "60") (name "Net-(LED46-DOUT)") (class "Default")
      (node (ref "LED46") (pin "2") (pinfunction "DOUT_2") (pintype "input"))
      (node (ref "LED47") (pin "4") (pinfunction "DIN_4") (pintype "input"))
    )
    (net (code "61") (name "Net-(LED47-DOUT)") (class "Default")
      (node (ref "LED47") (pin "2") (pinfunction "DOUT_2") (pintype "input"))
      (node (ref "LED48") (pin "4") (pinfunction "DIN_4") (pintype "input"))
    )
    (net (code "62") (name "Net-(LED48-DOUT)") (class "Default")
      (node (ref "LED48") (pin "2") (pinfunction "DOUT_2") (pintype "input"))
      (node (ref "LED49") (pin "4") (pinfunction "DIN_4") (pintype "input"))
    )
    (net (code "63") (name "Net-(LED49-DOUT)") (class "Default")
      (node (ref "LED49") (pin "2") (pinfunction "DOUT_2") (pintype "input"))
      (node (ref "LED50") (pin "4") (pinfunction "DIN_4") (pintype "input"))
    )
    (net (code "64") (name "Net-(LED50-DOUT)") (class "Default")
      (node (ref "LED50") (pin "2") (pinfunction "DOUT_2") (pintype "input"))
      (node (ref "LED51") (pin "4") (pinfunction "DIN_4") (pintype "input"))
    )
    (net (code "65") (name "Net-(LED51-DOUT)") (class "Default")
      (node (ref "LED51") (pin "2") (pinfunction "DOUT_2") (pintype "input"))
      (node (ref "LED52") (pin "4") (pinfunction "DIN_4") (pintype "input"))
    )
    (net (code "66") (name "Net-(LED52-DOUT)") (class "Default")
      (node (ref "LED52") (pin "2") (pinfunction "DOUT_2") (pintype "input"))
      (node (ref "LED53") (pin "4") (pinfunction "DIN_4") (pintype "input"))
    )
    (net (code "67") (name "Net-(LED53-DOUT)") (class "Default")
      (node (ref "LED53") (pin "2") (pinfunction "DOUT_2") (pintype "input"))
      (node (ref "LED54") (pin "4") (pinfunction "DIN_4") (pintype "input"))
    )
    (net (code "68") (name "Net-(LED54-DOUT)") (class "Default")
      (node (ref "LED54") (pin "2") (pinfunction "DOUT_2") (pintype "input"))
      (node (ref "LED55") (pin "4") (pinfunction "DIN_4") (pintype "input"))
    )
    (net (code "69") (name "Net-(LED55-DOUT)") (class "Default")
      (node (ref "LED55") (pin "2") (pinfunction "DOUT_2") (pintype "input"))
      (node (ref "LED56") (pin "4") (pinfunction "DIN_4") (pintype "input"))
    )
    (net (code "70") (name "Net-(LED56-DOUT)") (class "Default")
      (node (ref "LED56") (pin "2") (pinfunction "DOUT_2") (pintype "input"))
      (node (ref "LED57") (pin "4") (pinfunction "DIN_4") (pintype "input"))
    )
    (net (code "71") (name "Net-(LED57-DOUT)") (class "Default")
      (node (ref "LED57") (pin "2") (pinfunction "DOUT_2") (pintype "input"))
      (node (ref "LED58") (pin "4") (pinfunction "DIN_4") (pintype "input"))
    )
    (net (code "72") (name "Net-(LED58-DOUT)") (class "Default")
      (node (ref "LED58") (pin "2") (pinfunction "DOUT_2") (pintype "input"))
      (node (ref "LED59") (pin "4") (pinfunction "DIN_4") (pintype "input"))
    )
    (net (code "73") (name "Net-(LED59-DOUT)") (class "Default")
      (node (ref "LED59") (pin "2") (pinfunction "DOUT_2") (pintype "input"))
      (node (ref "LED60") (pin "4") (pinfunction "DIN_4") (pintype "input"))
    )
    (net (code "74") (name "Net-(LED60-DOUT)") (class "Default")
      (node (ref "LED60") (pin "2") (pinfunction "DOUT_2") (pintype "input"))
      (node (ref "LED61") (pin "4") (pinfunction "DIN_4") (pintype "input"))
    )
    (net (code "75") (name "Net-(LED61-DOUT)") (class "Default")
      (node (ref "LED61") (pin "2") (pinfunction "DOUT_2") (pintype "input"))
      (node (ref "LED62") (pin "4") (pinfunction "DIN_4") (pintype "input"))
    )
    (net (code "76") (name "Net-(LED62-DOUT)") (class "Default")
      (node (ref "LED62") (pin "2") (pinfunction "DOUT_2") (pintype "input"))
      (node (ref "LED63") (pin "4") (pinfunction "DIN_4") (pintype "input"))
    )
    (net (code "77") (name "Net-(LED63-DOUT)") (class "Default")
      (node (ref "LED63") (pin "2") (pinfunction "DOUT_2") (pintype "input"))
      (node (ref "LED64") (pin "4") (pinfunction "DIN_4") (pintype "input"))
    )
    (net (code "78") (name "Net-(Q5-VIN)") (class "Default")
      (node (ref "C104") (pin "2") (pinfunction "2_2") (pintype "input"))
      (node (ref "Q5") (pin "3") (pinfunction "VIN_3") (pintype "input"))
    )
    (net (code "79") (name "Net-(U1-IO2)") (class "Default")
      (node (ref "R4") (pin "2") (pinfunction "2_2") (pintype "input"))
      (node (ref "U1") (pin "24") (pinfunction "IO2_24") (pintype "input"))
    )
    (net (code "80") (name "Net-(U3-RST#)") (class "Default")
      (node (ref "R3") (pin "2") (pinfunction "2_2") (pintype "input"))
      (node (ref "U3") (pin "9") (pinfunction "RST#_9") (pintype "input"))
    )
    (net (code "81") (name "Net-(U9-VCC1)") (class "Default")
      (node (ref "C105") (pin "1") (pinfunction "1_1") (pintype "input"))
      (node (ref "U9") (pin "8") (pinfunction "VCC1_8") (pintype "input"))
    )
    (net (code "82") (name "Net-(U9-X1)") (class "Default")
      (node (ref "U9") (pin "2") (pinfunction "X1_2") (pintype "input"))
      (node (ref "X1") (pin "1") (pinfunction "OSC1_1") (pintype "input"))
    )
    (net (code "83") (name "Net-(U9-X2)") (class "Default")
      (node (ref "U9") (pin "3") (pinfunction "X2_3") (pintype "input"))
      (node (ref "X1") (pin "4") (pinfunction "OSC2_4") (pintype "input"))
    )
    (net (code "84") (name "Net-(USB1-CC1)") (class "Default")
      (node (ref "R2") (pin "1") (pinfunction "1_1") (pintype "input"))
      (node (ref "USB1") (pin "A5") (pinfunction "CC1_A5") (pintype "input"))
    )
    (net (code "85") (name "Net-(USB1-CC2)") (class "Default")
      (node (ref "R1") (pin "2") (pinfunction "2_2") (pintype "input"))
      (node (ref "USB1") (pin "B5") (pinfunction "CC2_B5") (pintype "input"))
    )
    (net (code "86") (name "RTS") (class "Default")
      (node (ref "Q4") (pin "1") (pinfunction "E_1") (pintype "input"))
      (node (ref "Q4") (pin "5") (pinfunction "B_5") (pintype "input"))
      (node (ref "U3") (pin "24") (pinfunction "RTS_24") (pintype "input"))
    )
    (net (code "87") (name "SHT_SCL") (class "Default")
      (node (ref "R27") (pin "1") (pinfunction "1_1") (pintype "input"))
      (node (ref "U1") (pin "11") (pinfunction "IO26_11") (pintype "input"))
      (node (ref "U8") (pin "4") (pinfunction "SCL_4") (pintype "input"))
    )
    (net (code "88") (name "SHT_SDA") (class "Default")
      (node (ref "R26") (pin "1") (pinfunction "1_1") (pintype "input"))
      (node (ref "U1") (pin "12") (pinfunction "IO27_12") (pintype "input"))
      (node (ref "U8") (pin "1") (pinfunction "SDA_1") (pintype "input"))
    )
    (net (code "89") (name "VCC") (class "Default")
      (node (ref "C15") (pin "1") (pinfunction "1_1") (pintype "input"))
      (node (ref "D1") (pin "1") (pinfunction "K_1") (pintype "input"))
      (node (ref "R3") (pin "1") (pinfunction "1_1") (pintype "input"))
      (node (ref "R5") (pin "1") (pinfunction "1_1") (pintype "input"))
      (node (ref "U3") (pin "7") (pinfunction "REGIN_7") (pintype "input"))
      (node (ref "U3") (pin "8") (pinfunction "VBUS_8") (pintype "input"))
    )
    (net (code "90") (name "VLED") (class "Default")
      (node (ref "C2") (pin "2") (pinfunction "2_2") (pintype "input"))
      (node (ref "C3") (pin "2") (pinfunction "2_2") (pintype "input"))
      (node (ref "C4") (pin "2") (pinfunction "2_2") (pintype "input"))
      (node (ref "C5") (pin "2") (pinfunction "2_2") (pintype "input"))
      (node (ref "C6") (pin "2") (pinfunction "2_2") (pintype "input"))
      (node (ref "C7") (pin "2") (pinfunction "2_2") (pintype "input"))
      (node (ref "C8") (pin "2") (pinfunction "2_2") (pintype "input"))
      (node (ref "C9") (pin "2") (pinfunction "2_2") (pintype "input"))
      (node (ref "LED1") (pin "1") (pinfunction "VDD_1") (pintype "input"))
      (node (ref "LED10") (pin "1") (pinfunction "VDD_1") (pintype "input"))
      (node (ref "LED11") (pin "1") (pinfunction "VDD_1") (pintype "input"))
      (node (ref "LED12") (pin "1") (pinfunction "VDD_1") (pintype "input"))
      (node (ref "LED13") (pin "1") (pinfunction "VDD_1") (pintype "input"))
      (node (ref "LED14") (pin "1") (pinfunction "VDD_1") (pintype "input"))
      (node (ref "LED15") (pin "1") (pinfunction "VDD_1") (pintype "input"))
      (node (ref "LED16") (pin "1") (pinfunction "VDD_1") (pintype "input"))
      (node (ref "LED17") (pin "1") (pinfunction "VDD_1") (pintype "input"))
      (node (ref "LED18") (pin "1") (pinfunction "VDD_1") (pintype "input"))
      (node (ref "LED19") (pin "1") (pinfunction "VDD_1") (pintype "input"))
      (node (ref "LED2") (pin "1") (pinfunction "VDD_1") (pintype "input"))
      (node (ref "LED20") (pin "1") (pinfunction "VDD_1") (pintype "input"))
      (node (ref "LED21") (pin "1") (pinfunction "VDD_1") (pintype "input"))
      (node (ref "LED22") (pin "1") (pinfunction "VDD_1") (pintype "input"))
      (node (ref "LED23") (pin "1") (pinfunction "VDD_1") (pintype "input"))
      (node (ref "LED24") (pin "1") (pinfunction "VDD_1") (pintype "input"))
      (node (ref "LED25") (pin "1") (pinfunction "VDD_1") (pintype "input"))
      (node (ref "LED26") (pin "1") (pinfunction "VDD_1") (pintype "input"))
      (node (ref "LED27") (pin "1") (pinfunction "VDD_1") (pintype "input"))
      (node (ref "LED28") (pin "1") (pinfunction "VDD_1") (pintype "input"))
      (node (ref "LED29") (pin "1") (pinfunction "VDD_1") (pintype "input"))
      (node (ref "LED3") (pin "1") (pinfunction "VDD_1") (pintype "input"))
      (node (ref "LED30") (pin "1") (pinfunction "VDD_1") (pintype "input"))
      (node (ref "LED31") (pin "1") (pinfunction "VDD_1") (pintype "input"))
      (node (ref "LED32") (pin "1") (pinfunction "VDD_1") (pintype "input"))
      (node (ref "LED33") (pin "1") (pinfunction "VDD_1") (pintype "input"))
      (node (ref "LED34") (pin "1") (pinfunction "VDD_1") (pintype "input"))
      (node (ref "LED35") (pin "1") (pinfunction "VDD_1") (pintype "input"))
      (node (ref "LED36") (pin "1") (pinfunction "VDD_1") (pintype "input"))
      (node (ref "LED37") (pin "1") (pinfunction "VDD_1") (pintype "input"))
      (node (ref "LED38") (pin "1") (pinfunction "VDD_1") (pintype "input"))
      (node (ref "LED39") (pin "1") (pinfunction "VDD_1") (pintype "input"))
      (node (ref "LED4") (pin "1") (pinfunction "VDD_1") (pintype "input"))
      (node (ref "LED40") (pin "1") (pinfunction "VDD_1") (pintype "input"))
      (node (ref "LED41") (pin "1") (pinfunction "VDD_1") (pintype "input"))
      (node (ref "LED42") (pin "1") (pinfunction "VDD_1") (pintype "input"))
      (node (ref "LED43") (pin "1") (pinfunction "VDD_1") (pintype "input"))
      (node (ref "LED44") (pin "1") (pinfunction "VDD_1") (pintype "input"))
      (node (ref "LED45") (pin "1") (pinfunction "VDD_1") (pintype "input"))
      (node (ref "LED46") (pin "1") (pinfunction "VDD_1") (pintype "input"))
      (node (ref "LED47") (pin "1") (pinfunction "VDD_1") (pintype "input"))
      (node (ref "LED48") (pin "1") (pinfunction "VDD_1") (pintype "input"))
      (node (ref "LED49") (pin "1") (pinfunction "VDD_1") (pintype "input"))
      (node (ref "LED5") (pin "1") (pinfunction "VDD_1") (pintype "input"))
      (node (ref "LED50") (pin "1") (pinfunction "VDD_1") (pintype "input"))
      (node (ref "LED51") (pin "1") (pinfunction "VDD_1") (pintype "input"))
      (node (ref "LED52") (pin "1") (pinfunction "VDD_1") (pintype "input"))
      (node (ref "LED53") (pin "1") (pinfunction "VDD_1") (pintype "input"))
      (node (ref "LED54") (pin "1") (pinfunction "VDD_1") (pintype "input"))
      (node (ref "LED55") (pin "1") (pinfunction "VDD_1") (pintype "input"))
      (node (ref "LED56") (pin "1") (pinfunction "VDD_1") (pintype "input"))
      (node (ref "LED57") (pin "1") (pinfunction "VDD_1") (pintype "input"))
      (node (ref "LED58") (pin "1") (pinfunction "VDD_1") (pintype "input"))
      (node (ref "LED59") (pin "1") (pinfunction "VDD_1") (pintype "input"))
      (node (ref "LED6") (pin "1") (pinfunction "VDD_1") (pintype "input"))
      (node (ref "LED60") (pin "1") (pinfunction "VDD_1") (pintype "input"))
      (node (ref "LED61") (pin "1") (pinfunction "VDD_1") (pintype "input"))
      (node (ref "LED62") (pin "1") (pinfunction "VDD_1") (pintype "input"))
      (node (ref "LED63") (pin "1") (pinfunction "VDD_1") (pintype "input"))
      (node (ref "LED64") (pin "1") (pinfunction "VDD_1") (pintype "input"))
      (node (ref "LED7") (pin "1") (pinfunction "VDD_1") (pintype "input"))
      (node (ref "LED8") (pin "1") (pinfunction "VDD_1") (pintype "input"))
      (node (ref "LED9") (pin "1") (pinfunction "VDD_1") (pintype "input"))
      (node (ref "R5") (pin "2") (pinfunction "2_2") (pintype "input"))
    )
    (net (code "91") (name "VUSB") (class "Default")
      (node (ref "D1") (pin "2") (pinfunction "A_2") (pintype "input"))
      (node (ref "USB1") (pin "A4") (pinfunction "VBUS_A4") (pintype "input"))
      (node (ref "USB1") (pin "A9") (pinfunction "VBUS_A9") (pintype "input"))
      (node (ref "USB1") (pin "B4") (pinfunction "VBUS_B4") (pintype "input"))
      (node (ref "USB1") (pin "B9") (pinfunction "VBUS_B9") (pintype "input"))
    )
    (net (code "92") (name "unconnected-(U1-CLK-Pad20)") (class "Default")
      (node (ref "U1") (pin "20") (pinfunction "CLK_20") (pintype "input"))
    )
    (net (code "93") (name "unconnected-(U1-CMD-Pad19)") (class "Default")
      (node (ref "U1") (pin "19") (pinfunction "CMD_19") (pintype "input"))
    )
    (net (code "94") (name "unconnected-(U1-IO4-Pad26)") (class "Default")
      (node (ref "U1") (pin "26") (pinfunction "IO4_26") (pintype "input"))
    )
    (net (code "95") (name "unconnected-(U1-IO5-Pad29)") (class "Default")
      (node (ref "U1") (pin "29") (pinfunction "IO5_29") (pintype "input"))
    )
    (net (code "96") (name "unconnected-(U1-IO12-Pad14)") (class "Default")
      (node (ref "U1") (pin "14") (pinfunction "IO12_14") (pintype "input"))
    )
    (net (code "97") (name "unconnected-(U1-IO13-Pad16)") (class "Default")
      (node (ref "U1") (pin "16") (pinfunction "IO13_16") (pintype "input"))
    )
    (net (code "98") (name "unconnected-(U1-IO14-Pad13)") (class "Default")
      (node (ref "U1") (pin "13") (pinfunction "IO14_13") (pintype "input"))
    )
    (net (code "99") (name "unconnected-(U1-IO15-Pad23)") (class "Default")
      (node (ref "U1") (pin "23") (pinfunction "IO15_23") (pintype "input"))
    )
    (net (code "100") (name "unconnected-(U1-IO16-Pad27)") (class "Default")
      (node (ref "U1") (pin "27") (pinfunction "IO16_27") (pintype "input"))
    )
    (net (code "101") (name "unconnected-(U1-IO17-Pad28)") (class "Default")
      (node (ref "U1") (pin "28") (pinfunction "IO17_28") (pintype "input"))
    )
    (net (code "102") (name "unconnected-(U1-IO18-Pad30)") (class "Default")
      (node (ref "U1") (pin "30") (pinfunction "IO18_30") (pintype "input"))
    )
    (net (code "103") (name "unconnected-(U1-IO19-Pad31)") (class "Default")
      (node (ref "U1") (pin "31") (pinfunction "IO19_31") (pintype "input"))
    )
    (net (code "104") (name "unconnected-(U1-IO21-Pad33)") (class "Default")
      (node (ref "U1") (pin "33") (pinfunction "IO21_33") (pintype "input"))
    )
    (net (code "105") (name "unconnected-(U1-IO22-Pad36)") (class "Default")
      (node (ref "U1") (pin "36") (pinfunction "IO22_36") (pintype "input"))
    )
    (net (code "106") (name "unconnected-(U1-IO34-Pad6)") (class "Default")
      (node (ref "U1") (pin "6") (pinfunction "IO34_6") (pintype "input"))
    )
    (net (code "107") (name "unconnected-(U1-IO35-Pad7)") (class "Default")
      (node (ref "U1") (pin "7") (pinfunction "IO35_7") (pintype "input"))
    )
    (net (code "108") (name "unconnected-(U1-NC-Pad32)") (class "Default")
      (node (ref "U1") (pin "32") (pinfunction "NC_32") (pintype "input"))
    )
    (net (code "109") (name "unconnected-(U1-SD2-Pad17)") (class "Default")
      (node (ref "U1") (pin "17") (pinfunction "SD2_17") (pintype "input"))
    )
    (net (code "110") (name "unconnected-(U1-SD3-Pad18)") (class "Default")
      (node (ref "U1") (pin "18") (pinfunction "SD3_18") (pintype "input"))
    )
    (net (code "111") (name "unconnected-(U1-SDI-Pad22)") (class "Default")
      (node (ref "U1") (pin "22") (pinfunction "SDI_22") (pintype "input"))
    )
    (net (code "112") (name "unconnected-(U1-SDO-Pad21)") (class "Default")
      (node (ref "U1") (pin "21") (pinfunction "SDO_21") (pintype "input"))
    )
    (net (code "113") (name "unconnected-(U1-SENSOR_VN-Pad5)") (class "Default")
      (node (ref "U1") (pin "5") (pinfunction "SENSOR_VN_5") (pintype "input"))
    )
    (net (code "114") (name "unconnected-(U1-SENSOR_VP-Pad4)") (class "Default")
      (node (ref "U1") (pin "4") (pinfunction "SENSOR_VP_4") (pintype "input"))
    )
    (net (code "115") (name "unconnected-(U3-CTS-Pad23)") (class "Default")
      (node (ref "U3") (pin "23") (pinfunction "CTS_23") (pintype "input+no_connect"))
    )
    (net (code "116") (name "unconnected-(U3-DCD-Pad1)") (class "Default")
      (node (ref "U3") (pin "1") (pinfunction "DCD_1") (pintype "input+no_connect"))
    )
    (net (code "117") (name "unconnected-(U3-DSR-Pad27)") (class "Default")
      (node (ref "U3") (pin "27") (pinfunction "DSR_27") (pintype "input+no_connect"))
    )
    (net (code "118") (name "unconnected-(U3-NC-Pad10)") (class "Default")
      (node (ref "U3") (pin "10") (pinfunction "NC_10") (pintype "input+no_connect"))
    )
    (net (code "119") (name "unconnected-(U3-NC-Pad13)") (class "Default")
      (node (ref "U3") (pin "13") (pinfunction "NC_13") (pintype "input+no_connect"))
    )
    (net (code "120") (name "unconnected-(U3-NC-Pad14)") (class "Default")
      (node (ref "U3") (pin "14") (pinfunction "NC_14") (pintype "input+no_connect"))
    )
    (net (code "121") (name "unconnected-(U3-NC-Pad15)") (class "Default")
      (node (ref "U3") (pin "15") (pinfunction "NC_15") (pintype "input+no_connect"))
    )
    (net (code "122") (name "unconnected-(U3-NC-Pad16)") (class "Default")
      (node (ref "U3") (pin "16") (pinfunction "NC_16") (pintype "input+no_connect"))
    )
    (net (code "123") (name "unconnected-(U3-NC-Pad17)") (class "Default")
      (node (ref "U3") (pin "17") (pinfunction "NC_17") (pintype "input+no_connect"))
    )
    (net (code "124") (name "unconnected-(U3-NC-Pad18)") (class "Default")
      (node (ref "U3") (pin "18") (pinfunction "NC_18") (pintype "input+no_connect"))
    )
    (net (code "125") (name "unconnected-(U3-NC-Pad19)") (class "Default")
      (node (ref "U3") (pin "19") (pinfunction "NC_19") (pintype "input+no_connect"))
    )
    (net (code "126") (name "unconnected-(U3-NC-Pad20)") (class "Default")
      (node (ref "U3") (pin "20") (pinfunction "NC_20") (pintype "input+no_connect"))
    )
    (net (code "127") (name "unconnected-(U3-NC-Pad21)") (class "Default")
      (node (ref "U3") (pin "21") (pinfunction "NC_21") (pintype "input+no_connect"))
    )
    (net (code "128") (name "unconnected-(U3-NC-Pad22)") (class "Default")
      (node (ref "U3") (pin "22") (pinfunction "NC_22") (pintype "input+no_connect"))
    )
    (net (code "129") (name "unconnected-(U3-RI-Pad2)") (class "Default")
      (node (ref "U3") (pin "2") (pinfunction "RI_2") (pintype "input+no_connect"))
    )
    (net (code "130") (name "unconnected-(U3-SUSPEND#-Pad11)") (class "Default")
      (node (ref "U3") (pin "11") (pinfunction "SUSPEND#_11") (pintype "input+no_connect"))
    )
    (net (code "131") (name "unconnected-(U3-SUSPEND-Pad12)") (class "Default")
      (node (ref "U3") (pin "12") (pinfunction "SUSPEND_12") (pintype "input+no_connect"))
    )
    (net (code "132") (name "unconnected-(U3-VDD-Pad6)") (class "Default")
      (node (ref "U3") (pin "6") (pinfunction "VDD_6") (pintype "input+no_connect"))
    )
    (net (code "133") (name "unconnected-(U8-ALERT-Pad3)") (class "Default")
      (node (ref "U8") (pin "3") (pinfunction "ALERT_3") (pintype "input+no_connect"))
    )
    (net (code "134") (name "unconnected-(U8-nRESET-Pad6)") (class "Default")
      (node (ref "U8") (pin "6") (pinfunction "nRESET_6") (pintype "input+no_connect"))
    )
    (net (code "135") (name "unconnected-(USB1-SBU1-PadA8)") (class "Default")
      (node (ref "USB1") (pin "A8") (pinfunction "SBU1_A8") (pintype "input"))
    )
    (net (code "136") (name "unconnected-(USB1-SBU2-PadB8)") (class "Default")
      (node (ref "USB1") (pin "B8") (pinfunction "SBU2_B8") (pintype "input"))
    )
    (net (code "137") (name "unconnected-(X1-Pad2)") (class "Default")
      (node (ref "X1") (pin "2") (pinfunction "2_2") (pintype "input"))
    )
    (net (code "138") (name "unconnected-(X1-Pad3)") (class "Default")
      (node (ref "X1") (pin "3") (pinfunction "3_3") (pintype "input"))
    )
  )
)
